# CableNodeRevG.net
KiCad netlist of a schematic drawn in Altium Designer
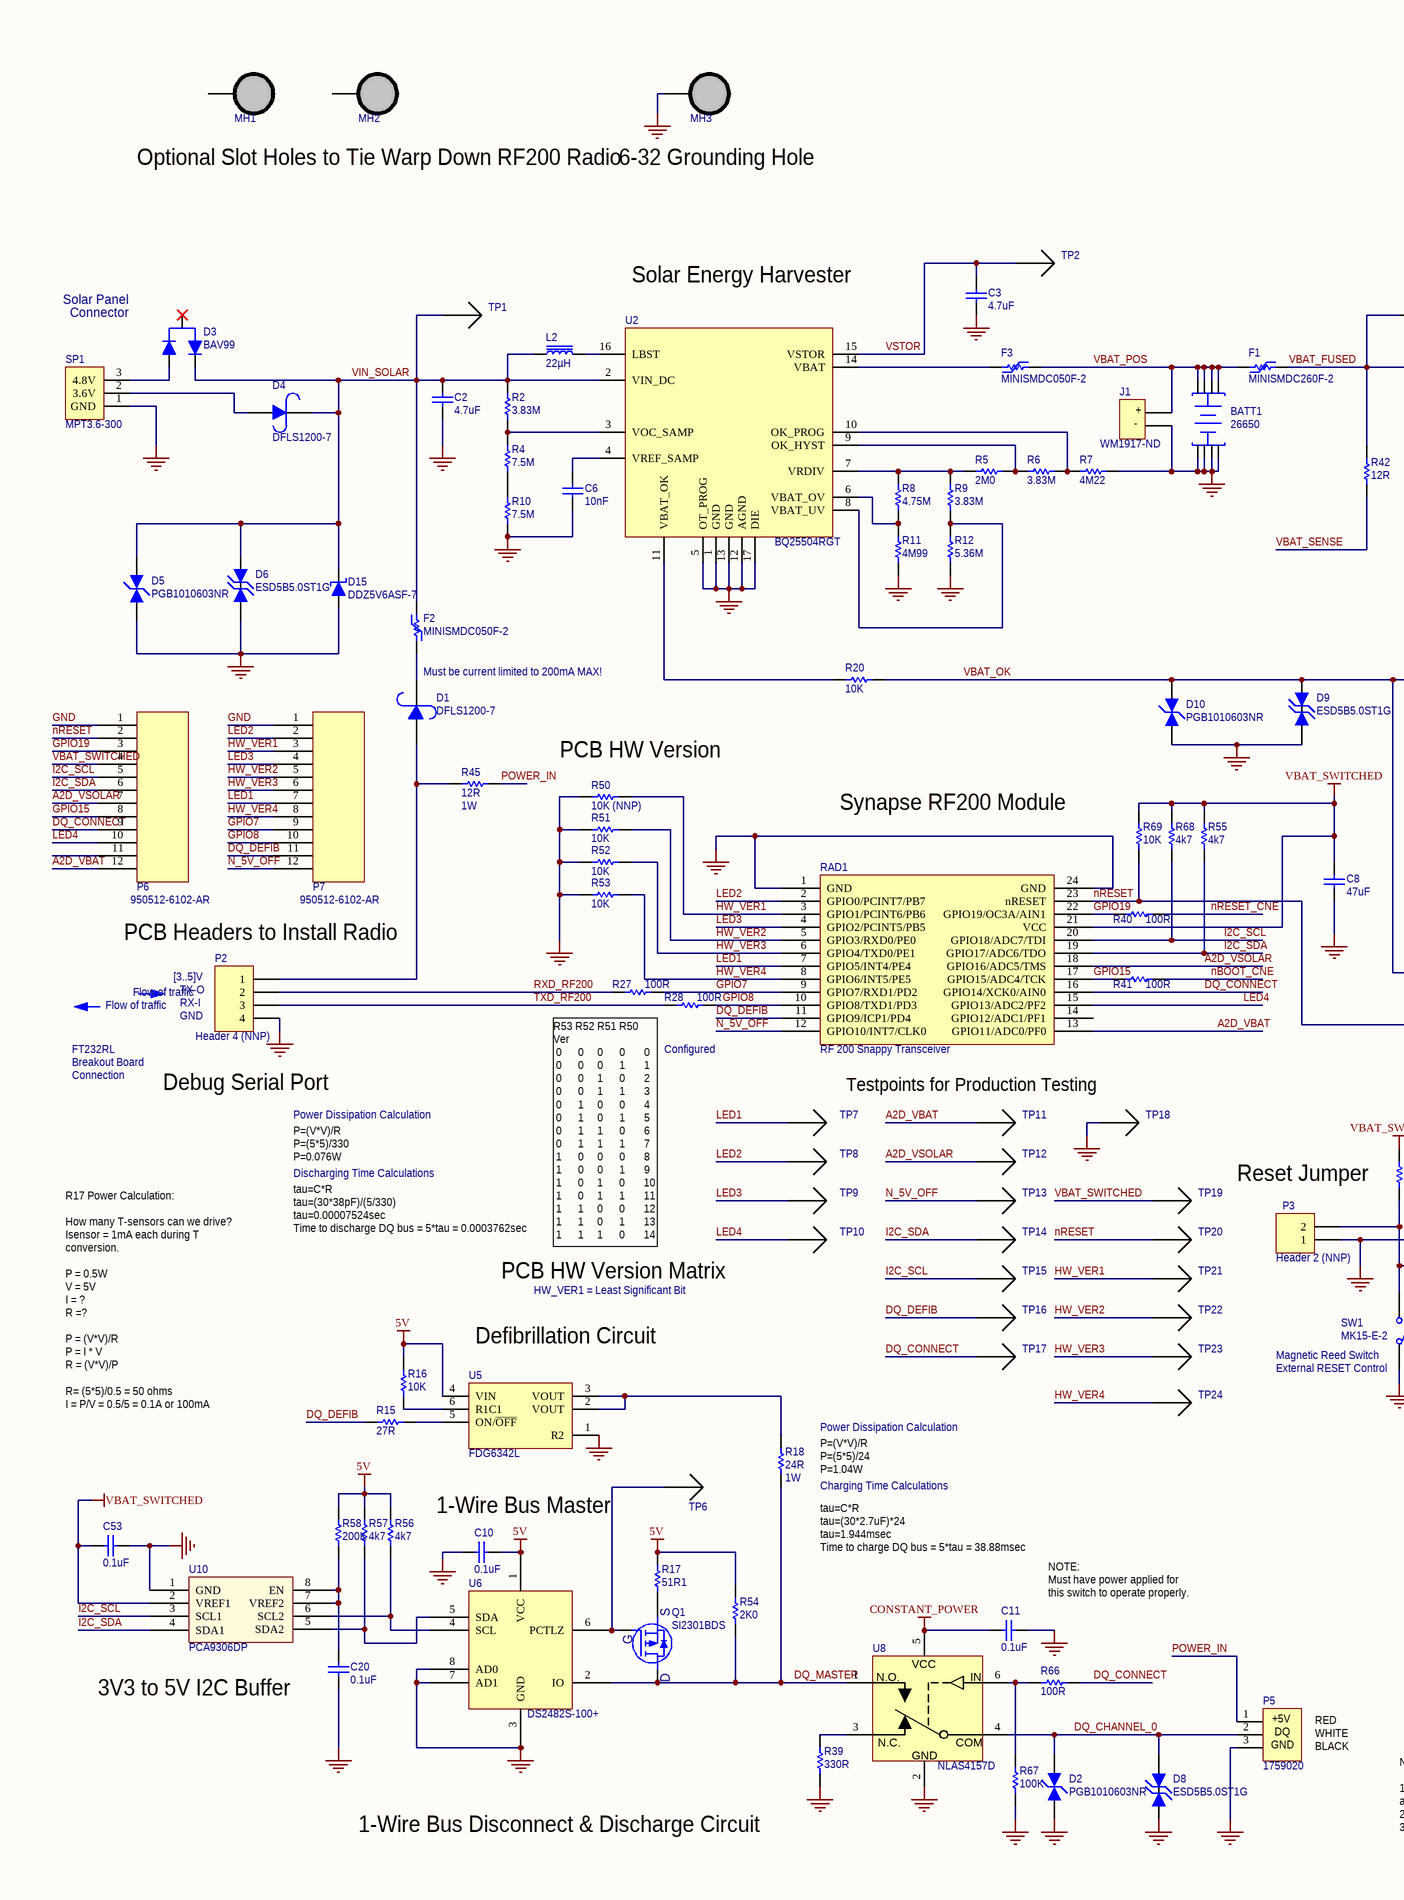
[diagram p0: CableNodeRevG.SchDoc, left]
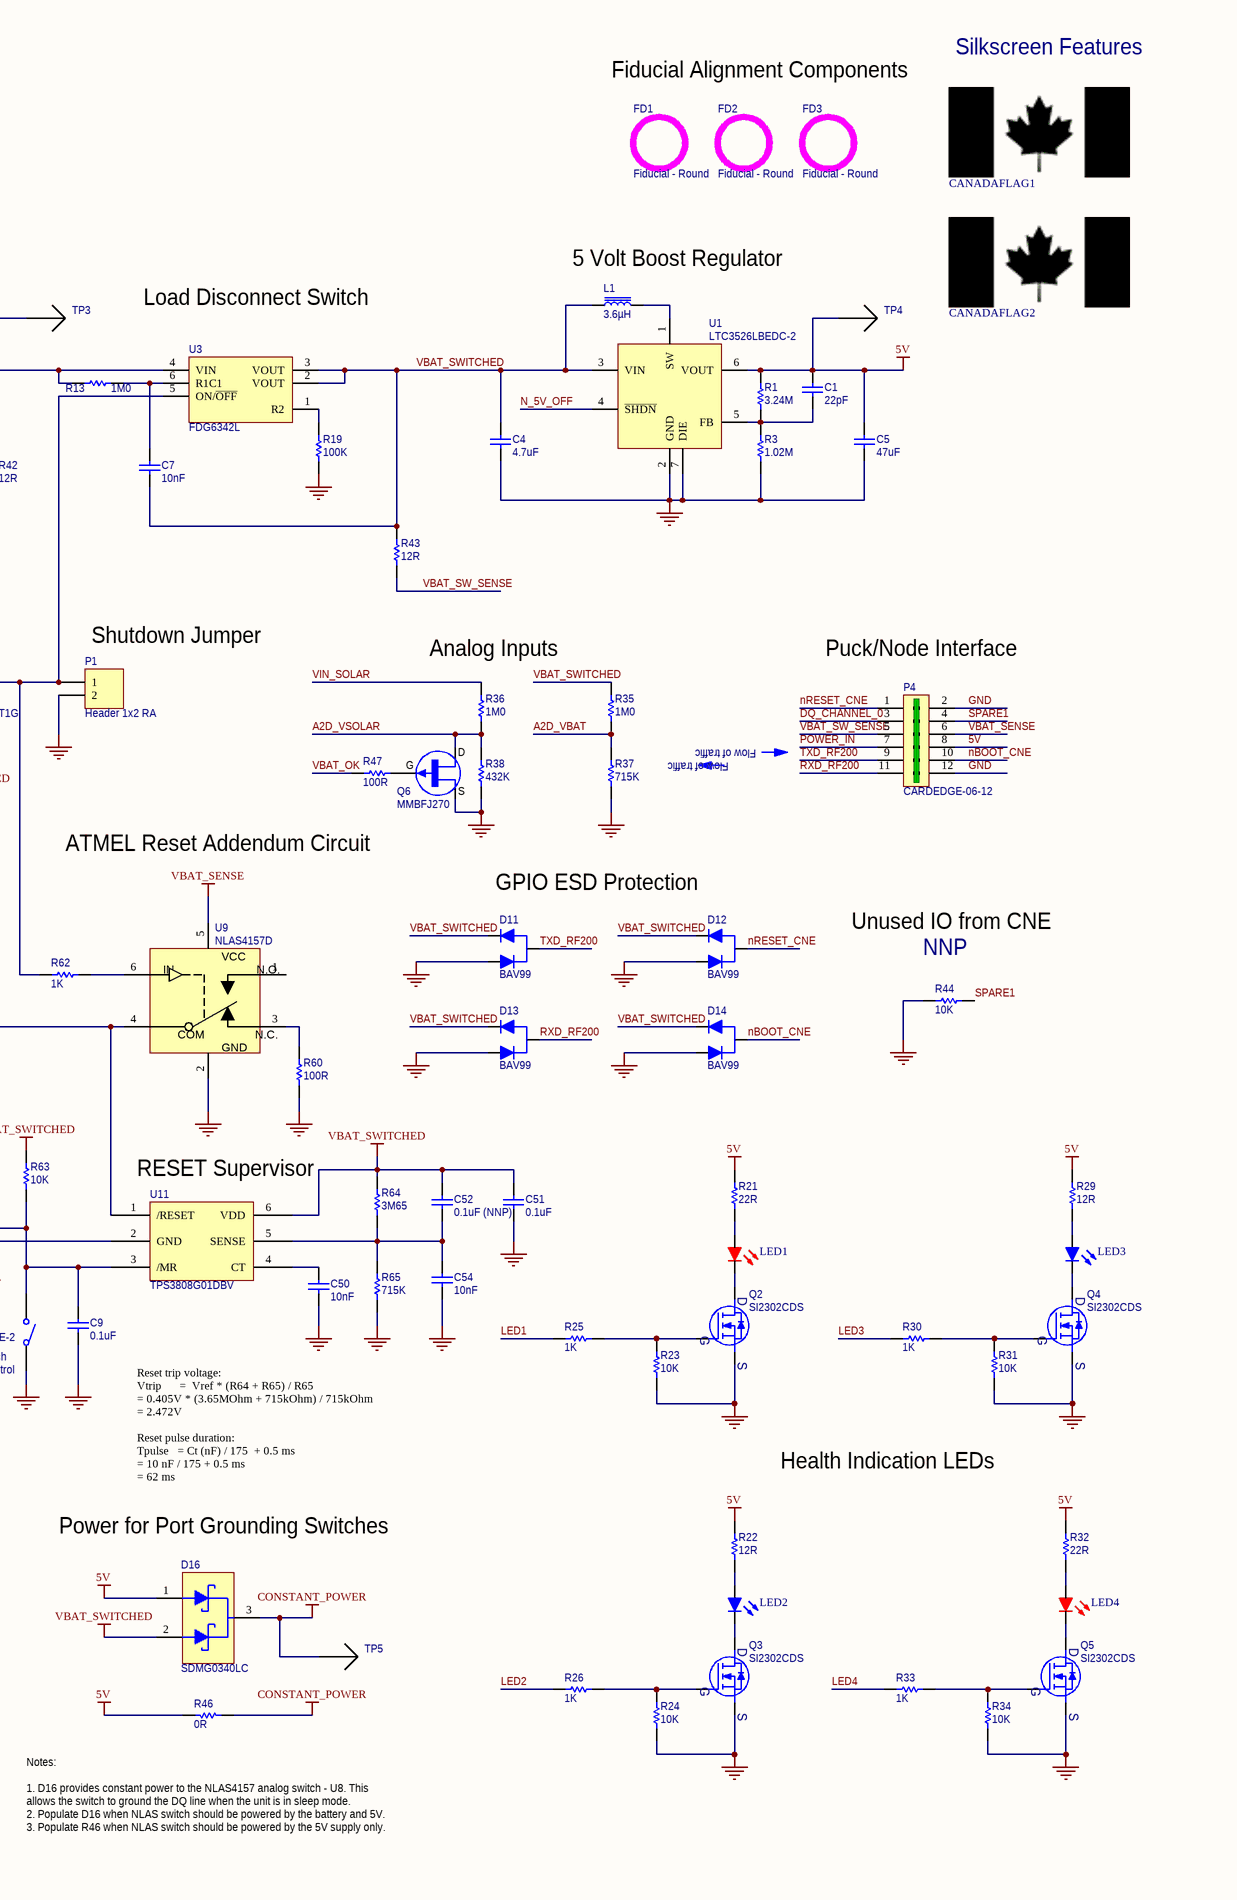
[diagram p1: CableNodeRevG.SchDoc, right]

(export (version "E")
  (design (tool "Eeschema 10.0.6"))
  (components
    (comp (ref "BATT1")
      (value "26650")
      (footprint "Battery_26650")
      (description "26650 LiFePO4 3.2V 3300mAh")
      (fields
        (field (name "MANUFACTURER") "TACBattery")
        (field (name "MANUFACTURER PART NUMBER") "26650 3.2V 1500mAh with wire")
      )
      (libsource (lib "Swage") (part "BATT_18650_1"))
    )
    (comp (ref "C1")
      (value "22pF")
      (footprint "RC0805")
      (description "CAP CER 22PF 50V 5% NPO 0805")
      (fields
        (field (name "MANUFACTURER") "Yageo")
        (field (name "MANUFACTURER PART NUMBER") "CC0805JRNPO9BN220")
      )
      (libsource (lib "Swage") (part "CC0805JRNPO9BN220"))
    )
    (comp (ref "C2")
      (value "4.7uF")
      (footprint "RC0805")
      (description "CAP CER 4.7UF 6.3V 10% X5R 0805")
      (fields
        (field (name "MANUFACTURER") "Taiyo Yuden")
        (field (name "MANUFACTURER PART NUMBER") "JMK212BJ475KG-T")
      )
      (libsource (lib "Swage") (part "JMK212BJ475KG-T"))
    )
    (comp (ref "C3")
      (value "4.7uF")
      (footprint "RC0805")
      (description "CAP CER 4.7UF 6.3V 10% X5R 0805")
      (fields
        (field (name "MANUFACTURER") "Taiyo Yuden")
        (field (name "MANUFACTURER PART NUMBER") "JMK212BJ475KG-T")
      )
      (libsource (lib "Swage") (part "JMK212BJ475KG-T"))
    )
    (comp (ref "C4")
      (value "4.7uF")
      (footprint "RC0805")
      (description "CAP CER 4.7UF 6.3V 10% X5R 0805")
      (fields
        (field (name "MANUFACTURER") "Taiyo Yuden")
        (field (name "MANUFACTURER PART NUMBER") "JMK212BJ475KG-T")
      )
      (libsource (lib "Swage") (part "JMK212BJ475KG-T"))
    )
    (comp (ref "C5")
      (value "47uF")
      (footprint "RC1206")
      (description "CAP CER 47UF 10V 20% X5R 1206")
      (fields
        (field (name "MANUFACTURER") "Taiyo Yuden")
        (field (name "MANUFACTURER PART NUMBER") "LMK316BJ476ML-T")
      )
      (libsource (lib "Swage") (part "LMK316BJ476ML-T"))
    )
    (comp (ref "C6")
      (value "10nF")
      (footprint "RC0805")
      (description "CAP CER 10000PF 100V X7R 0805")
      (fields
        (field (name "MANUFACTURER") "TDK Corporation")
        (field (name "MANUFACTURER PART NUMBER") "C2012X7R2A103K")
      )
      (libsource (lib "Swage") (part "C2012X7R2A103K"))
    )
    (comp (ref "C7")
      (value "10nF")
      (footprint "RC0603")
      (description "CAP CER 10000PF 50V 10% X7R 0603")
      (fields
        (field (name "MANUFACTURER") "TDK Corporation")
        (field (name "MANUFACTURER PART NUMBER") "C1608X7R1H103K")
      )
      (libsource (lib "Swage") (part "C1608X7R1H103K"))
    )
    (comp (ref "C8")
      (value "47uF")
      (footprint "RC1206")
      (description "CAP CER 47UF 10V 20% X5R 1206")
      (fields
        (field (name "MANUFACTURER") "Taiyo Yuden")
        (field (name "MANUFACTURER PART NUMBER") "LMK316BJ476ML-T")
      )
      (libsource (lib "Swage") (part "LMK316BJ476ML-T"))
    )
    (comp (ref "C9")
      (value "0.1uF")
      (footprint "RC0603")
      (description "CAP CERM .1UF 10% 16V X7R 0603")
      (fields
        (field (name "MANUFACTURER") "AVX Corporation")
        (field (name "MANUFACTURER PART NUMBER") "0603YC104KAT2A")
      )
      (libsource (lib "Swage") (part "0603YC104KAT2A"))
    )
    (comp (ref "C10")
      (value "0.1uF")
      (footprint "RC0603")
      (description "CAP CERM .1UF 10% 16V X7R 0603")
      (fields (field (name "TOLERANCE") "±10%") (field (name "MANUFACTURER PART NUMBER") "0603YC104KAT2A"))
      (libsource (lib "Swage") (part "0603YC104KAT2A"))
    )
    (comp (ref "C11")
      (value "0.1uF")
      (footprint "RC0603")
      (description "CAP CERM .1UF 10% 16V X7R 0603")
      (fields (field (name "TOLERANCE") "±10%") (field (name "MANUFACTURER PART NUMBER") "0603YC104KAT2A"))
      (libsource (lib "Swage") (part "0603YC104KAT2A"))
    )
    (comp (ref "C20")
      (value "0.1uF")
      (footprint "RC0603")
      (description "CAP CERM .1UF 10% 16V X7R 0603")
      (fields (field (name "TOLERANCE") "±10%") (field (name "MANUFACTURER PART NUMBER") "0603YC104KAT2A"))
      (libsource (lib "Swage") (part "0603YC104KAT2A"))
    )
    (comp (ref "C50")
      (value "10nF")
      (footprint "RC0603")
      (description "CAP CER 10000PF 50V 10% X7R 0603")
      (fields
        (field (name "MANUFACTURER") "TDK Corporation")
        (field (name "MANUFACTURER PART NUMBER") "C1608X7R1H103K")
      )
      (libsource (lib "Swage") (part "C1608X7R1H103K"))
    )
    (comp (ref "C51")
      (value "0.1uF")
      (footprint "RC0603")
      (description "CAP CERM .1UF 10% 16V X7R 0603")
      (fields (field (name "TOLERANCE") "±10%") (field (name "MANUFACTURER PART NUMBER") "0603YC104KAT2A"))
      (libsource (lib "Swage") (part "0603YC104KAT2A"))
    )
    (comp (ref "C52")
      (value "0.1uF (NNP)")
      (footprint "RC0603")
      (description "CAP CERM .1UF 10% 16V X7R 0603")
      (fields (field (name "TOLERANCE") "±10%") (field (name "MANUFACTURER PART NUMBER") "0603YC104KAT2A"))
      (libsource (lib "Swage") (part "0603YC104KAT2A"))
    )
    (comp (ref "C53")
      (value "0.1uF")
      (footprint "RC0603")
      (description "CAP CERM .1UF 10% 16V X7R 0603")
      (fields (field (name "TOLERANCE") "±10%") (field (name "MANUFACTURER PART NUMBER") "0603YC104KAT2A"))
      (libsource (lib "Swage") (part "0603YC104KAT2A"))
    )
    (comp (ref "C54")
      (value "10nF")
      (footprint "RC0603")
      (description "CAP CER 10000PF 50V 10% X7R 0603")
      (fields
        (field (name "MANUFACTURER") "TDK Corporation")
        (field (name "MANUFACTURER PART NUMBER") "C1608X7R1H103K")
      )
      (libsource (lib "Swage") (part "C1608X7R1H103K"))
    )
    (comp (ref "CANADAFLAG1")
      (value "Canada Flag")
      (footprint "CanadaFlag500x250")
      (libsource (lib "Swage") (part "CanadaFlag"))
    )
    (comp (ref "CANADAFLAG2")
      (value "Canada Flag")
      (footprint "CanadaFlag500x250")
      (libsource (lib "Swage") (part "CanadaFlag"))
    )
    (comp (ref "D1")
      (value "DFLS1200-7")
      (footprint "POWERDI-123")
      (description "DIODE SCHOTTKY 1A 200V PWRDI 123")
      (fields (field (name "MANUFACTURER") "Diodes Inc"))
      (libsource (lib "Swage") (part "DFLS1200-7"))
    )
    (comp (ref "D2")
      (value "PGB1010603NR")
      (footprint "RC0603")
      (description "SUPPRESSOR ESD 24VDC 0603 SMD")
      (fields (field (name "MANUFACTURER") "Littelfuse Inc"))
      (libsource (lib "Swage") (part "PGB1010603NR"))
    )
    (comp (ref "D3")
      (value "BAV99")
      (footprint "SOT23")
      (description "DIODE SW DUAL 75V 350MW SOT23-3")
      (fields
        (field (name "MANUFACTURER") "Diodes Inc")
        (field (name "MANUFACTURER PART NUMBER") "BAV99-7-F")
      )
      (libsource (lib "Swage") (part "BAV99-7-F"))
    )
    (comp (ref "D4")
      (value "DFLS1200-7")
      (footprint "POWERDI-123")
      (description "DIODE SCHOTTKY 1A 200V PWRDI 123")
      (fields (field (name "MANUFACTURER") "Diodes Inc"))
      (libsource (lib "Swage") (part "DFLS1200-7"))
    )
    (comp (ref "D5")
      (value "PGB1010603NR")
      (footprint "RC0603")
      (description "SUPPRESSOR ESD 24VDC 0603 SMD")
      (fields (field (name "MANUFACTURER") "Littelfuse Inc"))
      (libsource (lib "Swage") (part "PGB1010603NR"))
    )
    (comp (ref "D6")
      (value "ESD5B5.0ST1G")
      (footprint "SOD-523")
      (description "TVS BIDIRECT 50W SOD523")
      (fields (field (name "MANUFACTURER") "ON Semiconductor"))
      (libsource (lib "Swage") (part "ESD5B5.0ST1G"))
    )
    (comp (ref "D8")
      (value "ESD5B5.0ST1G")
      (footprint "SOD-523")
      (description "TVS BIDIRECT 50W SOD523")
      (fields (field (name "MANUFACTURER") "ON Semiconductor"))
      (libsource (lib "Swage") (part "ESD5B5.0ST1G"))
    )
    (comp (ref "D9")
      (value "ESD5B5.0ST1G")
      (footprint "SOD-523")
      (description "TVS BIDIRECT 50W SOD523")
      (fields (field (name "MANUFACTURER") "ON Semiconductor"))
      (libsource (lib "Swage") (part "ESD5B5.0ST1G"))
    )
    (comp (ref "D10")
      (value "PGB1010603NR")
      (footprint "RC0603")
      (description "SUPPRESSOR ESD 24VDC 0603 SMD")
      (fields (field (name "MANUFACTURER") "Littelfuse Inc"))
      (libsource (lib "Swage") (part "PGB1010603NR"))
    )
    (comp (ref "D11")
      (value "BAV99")
      (footprint "SOT23")
      (description "DIODE SW DUAL 75V 350MW SOT23-3")
      (fields
        (field (name "MANUFACTURER") "Diodes Inc")
        (field (name "MANUFACTURER PART NUMBER") "BAV99-7-F")
      )
      (libsource (lib "Swage") (part "BAV99-7-F"))
    )
    (comp (ref "D12")
      (value "BAV99")
      (footprint "SOT23")
      (description "DIODE SW DUAL 75V 350MW SOT23-3")
      (fields
        (field (name "MANUFACTURER") "Diodes Inc")
        (field (name "MANUFACTURER PART NUMBER") "BAV99-7-F")
      )
      (libsource (lib "Swage") (part "BAV99-7-F"))
    )
    (comp (ref "D13")
      (value "BAV99")
      (footprint "SOT23")
      (description "DIODE SW DUAL 75V 350MW SOT23-3")
      (fields
        (field (name "MANUFACTURER") "Diodes Inc")
        (field (name "MANUFACTURER PART NUMBER") "BAV99-7-F")
      )
      (libsource (lib "Swage") (part "BAV99-7-F"))
    )
    (comp (ref "D14")
      (value "BAV99")
      (footprint "SOT23")
      (description "DIODE SW DUAL 75V 350MW SOT23-3")
      (fields
        (field (name "MANUFACTURER") "Diodes Inc")
        (field (name "MANUFACTURER PART NUMBER") "BAV99-7-F")
      )
      (libsource (lib "Swage") (part "BAV99-7-F"))
    )
    (comp (ref "D15")
      (value "DDZ5V6ASF-7")
      (footprint "SOD323F")
      (description "DIODE ZENER 5.42V 500MW SOD323F")
      (fields (field (name "MANUFACTURER") "Diodes Inc") (field (name "TOLERANCE") "±2%"))
      (libsource (lib "Swage") (part "DDZ5V6ASF-7"))
    )
    (comp (ref "D16")
      (value "SDMG0340LC")
      (footprint "SOT-323")
      (description "DIODE SCHOTTKY 40V 30MA SOT323")
      (fields
        (field (name "MANUFACTURER") "Diodes Inc")
        (field (name "MANUFACTURER PART NUMBER") "SDMG0340LC-7-F")
      )
      (libsource (lib "Swage") (part "SDMG0340LC-7-F"))
    )
    (comp (ref "F1")
      (value "MINISMDC260F-2")
      (footprint "MINISMDC260F")
      (description "POLYSWITCH 2.6A RESET FUSE SMD")
      (fields (field (name "MANUFACTURER") "TE Connectivity"))
      (libsource (lib "Swage") (part "MINISMDC260F-2"))
    )
    (comp (ref "F2")
      (value "MINISMDC050F-2")
      (footprint "MINISMD050")
      (description "POLYSWITCH .50A RESET FUSE SMD")
      (fields (field (name "MANUFACTURER") "TE Connectivity"))
      (libsource (lib "Swage") (part "MINISMDC050F-2"))
    )
    (comp (ref "F3")
      (value "MINISMDC050F-2")
      (footprint "MINISMD050")
      (description "POLYSWITCH .50A RESET FUSE SMD")
      (fields (field (name "MANUFACTURER") "TE Connectivity"))
      (libsource (lib "Swage") (part "MINISMDC050F-2"))
    )
    (comp (ref "FD1")
      (value "Fiducial - Round")
      (footprint "FIDUCIAL ROUND SMALL")
      (description "Fiducial Round")
      (libsource (lib "StormaxV13") (part "Fiducial"))
    )
    (comp (ref "FD2")
      (value "Fiducial - Round")
      (footprint "FIDUCIAL ROUND SMALL")
      (description "Fiducial Round")
      (libsource (lib "StormaxV13") (part "Fiducial"))
    )
    (comp (ref "FD3")
      (value "Fiducial - Round")
      (footprint "FIDUCIAL ROUND SMALL")
      (description "Fiducial Round")
      (libsource (lib "StormaxV13") (part "Fiducial"))
    )
    (comp (ref "J1")
      (value "CONN")
      (footprint "BATTERYCONNECTOR")
      (description "CONN HEADER 2POS 3MM VERT GOLD")
      (fields
        (field (name "MANUFACTURER") "Molex Inc")
        (field (name "MANUFACTURER PART NUMBER") "436500216")
        (field (name "SUPPLIER PART NUMBER 1") "WM1917-ND")
      )
      (libsource (lib "Swage") (part "436500216"))
    )
    (comp (ref "L1")
      (value "3.6µH")
      (footprint "IND-WURTH")
      (description "INDUCTOR POWER 3.6UH 1.38A SMD")
      (fields
        (field (name "MANUFACTURER") "Wurth Electronics Inc")
        (field (name "MANUFACTURER PART NUMBER") "744031003")
      )
      (libsource (lib "Swage") (part "744031003"))
    )
    (comp (ref "L2")
      (value "22µH")
      (footprint "IND-SRR0604")
      (description "INDUCTOR PWR 22UH 20% SHIELD SMD")
      (fields
        (field (name "MANUFACTURER") "Bourns Inc.")
        (field (name "MANUFACTURER PART NUMBER") "SRR0604-220ML")
      )
      (libsource (lib "Swage") (part "SRR0604-220ML"))
    )
    (comp (ref "LED1")
      (value "GH_JTLPS1.24-K5L2-1-1-150-R33")
      (footprint "GHJTLPS124K5L211150R33")
      (description "LED")
      (fields
        (field (name "MANUFACTURER") "OSRAM")
        (field (name "MANUFACTURER PART NUMBER") "GH JTLPS1.24-K5L2-1-1-150-R33")
      )
      (libsource (lib "Swage") (part "GH_JTLPS1.24-K5L2-1-1-150-R33"))
    )
    (comp (ref "LED2")
      (value "GD JTLPS1.14-MFN8-25-1-150-R33")
      (footprint "GHJTLPS124K5L211150R33")
      (description "LED")
      (fields
        (field (name "MANUFACTURER") "OSRAM")
        (field (name "MANUFACTURER PART NUMBER") "GDJTLPS1.14-MFN8-25-1-150-R33")
      )
      (libsource (lib "Swage") (part "GH_JTLPS1.14-MFN8-25-1-150-R33"))
    )
    (comp (ref "LED3")
      (value "GD JTLPS1.14-MFN8-25-1-150-R33")
      (footprint "GHJTLPS124K5L211150R33")
      (description "LED")
      (fields
        (field (name "MANUFACTURER") "OSRAM")
        (field (name "MANUFACTURER PART NUMBER") "GDJTLPS1.14-MFN8-25-1-150-R33")
      )
      (libsource (lib "Swage") (part "GH_JTLPS1.14-MFN8-25-1-150-R33"))
    )
    (comp (ref "LED4")
      (value "GH_JTLPS1.24-K5L2-1-1-150-R33")
      (footprint "GHJTLPS124K5L211150R33")
      (description "LED")
      (fields
        (field (name "MANUFACTURER") "OSRAM")
        (field (name "MANUFACTURER PART NUMBER") "GH JTLPS1.24-K5L2-1-1-150-R33")
      )
      (libsource (lib "Swage") (part "GH_JTLPS1.24-K5L2-1-1-150-R33"))
    )
    (comp (ref "MH1")
      (value "MountingHole")
      (footprint "MountingHole")
      (description "PCB Mounting Hole, 0.150\" hole, 0.270\" Keepout")
      (libsource (lib "Swage") (part "MountingHole"))
    )
    (comp (ref "MH2")
      (value "MountingHole")
      (footprint "MountingHole")
      (description "PCB Mounting Hole, 0.150\" hole, 0.270\" Keepout")
      (libsource (lib "Swage") (part "MountingHole"))
    )
    (comp (ref "MH3")
      (value "MountingHole")
      (footprint "MountingHole")
      (description "PCB Mounting Hole, 0.150\" hole, 0.270\" Keepout")
      (libsource (lib "Swage") (part "MountingHole"))
    )
    (comp (ref "P1")
      (value "Header 1x2 RA")
      (footprint "HDR1X2")
      (description "SIL HORIZ PC TAIL PIN HEADER")
      (fields
        (field (name "MANUFACTURER") "Harwin Inc")
        (field (name "MANUFACTURER PART NUMBER") "M20-9960245")
      )
      (libsource (lib "Swage") (part "M20-9960245"))
    )
    (comp (ref "P2")
      (value "Header 4 (NNP)")
      (footprint "HDR1X4")
      (description "Header, 4-Pin")
      (fields
        (field (name "MANUFACTURER") "3M")
        (field (name "MANUFACTURER PART NUMBER") "2340-6111TG")
        (field (name "PUBLISHER") "Altium Limited")
      )
      (libsource (lib "Swage") (part "Header 4"))
    )
    (comp (ref "P3")
      (value "Header 2 (NNP)")
      (footprint "HDR1X2")
      (description "Header, 2-Pin")
      (fields
        (field (name "MANUFACTURER") "3M")
        (field (name "MANUFACTURER PART NUMBER") "2340-6111TG")
        (field (name "PUBLISHER") "Altium Limited")
      )
      (libsource (lib "Miscellaneous Connectors") (part "Header 2"))
    )
    (comp (ref "P4")
      (value "CARDEDGE-06-12")
      (footprint "EdgeConnectorFingers")
      (description "CONN EDGECARD 6POS .100 FINGERS")
      (libsource (lib "Swage") (part "CARDEDGE-06-12"))
    )
    (comp (ref "P5")
      (value "1759020")
      (footprint "PC-1759020")
      (description "CONN HEADER RT ANG 3POS 5.08MM")
      (fields (field (name "MANUFACTURER") "Phoenix Contact") (field (name "VOLTAGE") "300V"))
      (libsource (lib "Swage") (part "1759020"))
    )
    (comp (ref "P6")
      (value "3M-950512-6102-AR")
      (footprint "HEADER1X12-2MM")
      (description "CONN SOCKET 12POS 2MM VERT T/H")
      (fields (field (name "MANUFACTURER") "3M") (field (name "MANUFACTURER PART NUMBER") "950512-6102-AR"))
      (libsource (lib "Swage") (part "3M-950512-6102-AR"))
    )
    (comp (ref "P7")
      (value "3M-950512-6102-AR")
      (footprint "HEADER1X12-2MM")
      (description "CONN SOCKET 12POS 2MM VERT T/H")
      (fields (field (name "MANUFACTURER") "3M") (field (name "MANUFACTURER PART NUMBER") "950512-6102-AR"))
      (libsource (lib "Swage") (part "3M-950512-6102-AR"))
    )
    (comp (ref "Q1")
      (value "SI2301BDS")
      (footprint "SOT23(DGS)")
      (description "MOSFET P-CH 20V 2.2A SOT23-3")
      (fields
        (field (name "MANUFACTURER") "Vishay/Siliconix")
        (field (name "MANUFACTURER PART NUMBER") "SI2301BDS-T1-E3")
      )
      (libsource (lib "Swage") (part "SI2301BDS-T1-E3"))
    )
    (comp (ref "Q2")
      (value "SI2302CDS")
      (footprint "SOT23")
      (description "MOSFET N-CH 20V 2.6A SOT23-3")
      (fields
        (field (name "MANUFACTURER") "Vishay Siliconix")
        (field (name "MANUFACTURER PART NUMBER") "SI2302CDS-T1-GE3")
      )
      (libsource (lib "Swage") (part "SI2302CDS-T1-GE3"))
    )
    (comp (ref "Q3")
      (value "SI2302CDS")
      (footprint "SOT23")
      (description "MOSFET N-CH 20V 2.6A SOT23-3")
      (fields
        (field (name "MANUFACTURER") "Vishay Siliconix")
        (field (name "MANUFACTURER PART NUMBER") "SI2302CDS-T1-GE3")
      )
      (libsource (lib "Swage") (part "SI2302CDS-T1-GE3"))
    )
    (comp (ref "Q4")
      (value "SI2302CDS")
      (footprint "SOT23")
      (description "MOSFET N-CH 20V 2.6A SOT23-3")
      (fields
        (field (name "MANUFACTURER") "Vishay Siliconix")
        (field (name "MANUFACTURER PART NUMBER") "SI2302CDS-T1-GE3")
      )
      (libsource (lib "Swage") (part "SI2302CDS-T1-GE3"))
    )
    (comp (ref "Q5")
      (value "SI2302CDS")
      (footprint "SOT23")
      (description "MOSFET N-CH 20V 2.6A SOT23-3")
      (fields
        (field (name "MANUFACTURER") "Vishay Siliconix")
        (field (name "MANUFACTURER PART NUMBER") "SI2302CDS-T1-GE3")
      )
      (libsource (lib "Swage") (part "SI2302CDS-T1-GE3"))
    )
    (comp (ref "Q6")
      (value "MMBFJ270")
      (footprint "SOT23")
      (description "IC SWITCH P-CHANNEL SOT-23")
      (fields (field (name "MANUFACTURER") "Fairchild Semiconductor"))
      (libsource (lib "Swage") (part "MMBFJ270"))
    )
    (comp (ref "R1")
      (value "3.24M")
      (footprint "RC0805")
      (description "RES 3.24M OHM 1/8W 1% 0805 SMD")
      (fields
        (field (name "MANUFACTURER") "Vishay Dale")
        (field (name "MANUFACTURER PART NUMBER") "CRCW08053M24FKEA")
      )
      (libsource (lib "Swage") (part "CRCW08053M24FKEA"))
    )
    (comp (ref "R2")
      (value "3.83M")
      (footprint "RC0603")
      (description "RES 3.83M OHM 1/10W 1% 0603 SMD")
      (fields
        (field (name "MANUFACTURER") "Vishay Dale")
        (field (name "MANUFACTURER PART NUMBER") "CRCW06033M83FKEA")
      )
      (libsource (lib "Swage") (part "CRCW06033M83FKEA"))
    )
    (comp (ref "R3")
      (value "1.02M")
      (footprint "RC0805")
      (description "RES 1.02M OHM 1/8W 1% 0805 SMD")
      (fields
        (field (name "MANUFACTURER") "Vishay Dale")
        (field (name "MANUFACTURER PART NUMBER") "CRCW08051M02FKEA")
      )
      (libsource (lib "Swage") (part "CRCW08051M02FKEA"))
    )
    (comp (ref "R4")
      (value "7.5M")
      (footprint "RC0603")
      (description "RES 7.50M OHM 1/10W 1% 0603 SMD")
      (fields
        (field (name "MANUFACTURER") "Vishay Dale")
        (field (name "MANUFACTURER PART NUMBER") "CRCW06037M50FKEA")
      )
      (libsource (lib "Swage") (part "CRCW06037M50FKEA"))
    )
    (comp (ref "R5")
      (value "2M0")
      (footprint "RC0603")
      (description "RES 2.00M OHM 1/10W 1% 0603 SMD")
      (fields
        (field (name "MANUFACTURER") "Vishay Dale")
        (field (name "MANUFACTURER PART NUMBER") "CRCW06032M00FKEA")
      )
      (libsource (lib "Swage") (part "CRCW06032M00FKEA"))
    )
    (comp (ref "R6")
      (value "3.83M")
      (footprint "RC0603")
      (description "RES 3.83M OHM 1/10W 1% 0603 SMD")
      (fields
        (field (name "MANUFACTURER") "Vishay Dale")
        (field (name "MANUFACTURER PART NUMBER") "CRCW06033M83FKEA")
      )
      (libsource (lib "Swage") (part "CRCW06033M83FKEA"))
    )
    (comp (ref "R7")
      (value "4M22")
      (footprint "RC0603")
      (description "RES 4.22M OHM 1/10W 1% 0603 SMD")
      (fields
        (field (name "MANUFACTURER") "Vishay Dale")
        (field (name "MANUFACTURER PART NUMBER") "CRCW06034M22FKEA")
      )
      (libsource (lib "Swage") (part "CRCW06034M22FKEA"))
    )
    (comp (ref "R8")
      (value "4.75M")
      (footprint "rc0603")
      (description "RES 4.75M OHM 1/10W 1% 0603 SMD")
      (fields
        (field (name "MANUFACTURER") "Vishay Dale")
        (field (name "MANUFACTURER PART NUMBER") "CRCW06034M75FKEA")
      )
      (libsource (lib "Swage") (part "CRCW06034M75FKEA"))
    )
    (comp (ref "R9")
      (value "3.83M")
      (footprint "RC0603")
      (description "RES 3.83M OHM 1/10W 1% 0603 SMD")
      (fields
        (field (name "MANUFACTURER") "Vishay Dale")
        (field (name "MANUFACTURER PART NUMBER") "CRCW06033M83FKEA")
      )
      (libsource (lib "Swage") (part "CRCW06033M83FKEA"))
    )
    (comp (ref "R10")
      (value "7.5M")
      (footprint "RC0603")
      (description "RES 7.50M OHM 1/10W 1% 0603 SMD")
      (fields
        (field (name "MANUFACTURER") "Vishay Dale")
        (field (name "MANUFACTURER PART NUMBER") "CRCW06037M50FKEA")
      )
      (libsource (lib "Swage") (part "CRCW06037M50FKEA"))
    )
    (comp (ref "R11")
      (value "4M99")
      (footprint "rc0603")
      (description "RES 4.99M OHM 1/10W 1% 0603 SMD")
      (fields
        (field (name "MANUFACTURER") "Vishay Dale")
        (field (name "MANUFACTURER PART NUMBER") "CRCW06034M99FKEA")
      )
      (libsource (lib "Swage") (part "CRCW06034M99FKEA"))
    )
    (comp (ref "R12")
      (value "5.36M")
      (footprint "RC0603")
      (description "RES 5.36M OHM 1/10W 1% 0603 SMD")
      (fields
        (field (name "MANUFACTURER") "Vishay Dale")
        (field (name "MANUFACTURER PART NUMBER") "CRCW06035M36FKEA")
      )
      (libsource (lib "Swage") (part "CRCW06035M36FKEA (2)"))
    )
    (comp (ref "R13")
      (value "1M0")
      (footprint "RESC1608X06N")
      (description "RES 1.0M OHM 1/10W 5% 0603 SMD")
      (fields (field (name "TOLERANCE") "±5%") (field (name "MANUFACTURER") "Panasonic - ECG"))
      (libsource (lib "Swage") (part "ERJ-3GEYJ105V"))
    )
    (comp (ref "R15")
      (value "27R")
      (footprint "RC0603")
      (description "RES 27.0 OHM 1/10W 1% 0603 SMD")
      (fields
        (field (name "MANUFACTURER") "Panasonic Electronic Components")
        (field (name "MANUFACTURER PART NUMBER") "ERJ-3EKF27R0V")
      )
      (libsource (lib "Swage") (part "ERJ-3EKF27R0V"))
    )
    (comp (ref "R16")
      (value "10K")
      (footprint "RC0603")
      (description "RES 10K OHM 1/10W 5% 0603 SMD")
      (fields
        (field (name "MANUFACTURER") "Panasonic Electronic Components")
        (field (name "MANUFACTURER PART NUMBER") "ERJ-3GEYJ103V")
      )
      (libsource (lib "Swage") (part "ERJ-3GEYJ103V"))
    )
    (comp (ref "R17")
      (value "51R1")
      (footprint "RC3225X07N")
      (description "RES 51.1 OHM 1/2W 1% 1210 SMD")
      (fields
        (field (name "MANUFACTURER") "Panasonic Electronic Components")
        (field (name "MANUFACTURER PART NUMBER") "ERJ-14NF51R1U")
      )
      (libsource (lib "Swage") (part "ERJ-14NF51R1U"))
    )
    (comp (ref "R18")
      (value "24R")
      (footprint "RES2512")
      (description "RES 24 OHM 1W 5% 2512 SMD")
      (fields
        (field (name "MANUFACTURER") "TTI Inc.")
        (field (name "MANUFACTURER PART NUMBER") "CRCW251224R0JNEG")
        (field (name "POWER (WATTS)") "1W")
      )
      (libsource (lib "Swage") (part "RMCF2512JT24R0"))
    )
    (comp (ref "R19")
      (value "100K")
      (footprint "RC0603")
      (description "RES 100K OHM 1/10W 5% 0603 SMD")
      (fields
        (field (name "MANUFACTURER") "Panasonic Electronic Components")
        (field (name "MANUFACTURER PART NUMBER") "ERJ-3GEYJ104V")
      )
      (libsource (lib "Swage") (part "ERJ-3GEYJ104V"))
    )
    (comp (ref "R20")
      (value "10K")
      (footprint "RC0603")
      (description "RES 10K OHM 1/10W 5% 0603 SMD")
      (fields
        (field (name "MANUFACTURER") "Panasonic Electronic Components")
        (field (name "MANUFACTURER PART NUMBER") "ERJ-3GEYJ103V")
      )
      (libsource (lib "Swage") (part "ERJ-3GEYJ103V"))
    )
    (comp (ref "R21")
      (value "22R")
      (footprint "RC1206")
      (description "RES 22.0 OHM 1/4W 1% 1206 SMD")
      (fields
        (field (name "MANUFACTURER") "Yageo")
        (field (name "MANUFACTURER PART NUMBER") "RC1206FR-0722RL")
      )
      (libsource (lib "Swage") (part "RC1206FR-0722RL"))
    )
    (comp (ref "R22")
      (value "12R")
      (footprint "RC1206")
      (description "RES 12.0 OHM 1/4W 1% 1206 SMD")
      (fields
        (field (name "MANUFACTURER") "Yageo")
        (field (name "MANUFACTURER PART NUMBER") "RC1206FR-0712RL")
      )
      (libsource (lib "Swage") (part "RC1206FR-0712RL"))
    )
    (comp (ref "R23")
      (value "10K")
      (footprint "RC0603")
      (description "RES 10K OHM 1/10W 5% 0603 SMD")
      (fields
        (field (name "MANUFACTURER") "Panasonic Electronic Components")
        (field (name "MANUFACTURER PART NUMBER") "ERJ-3GEYJ103V")
      )
      (libsource (lib "Swage") (part "ERJ-3GEYJ103V"))
    )
    (comp (ref "R24")
      (value "10K")
      (footprint "RC0603")
      (description "RES 10K OHM 1/10W 5% 0603 SMD")
      (fields
        (field (name "MANUFACTURER") "Panasonic Electronic Components")
        (field (name "MANUFACTURER PART NUMBER") "ERJ-3GEYJ103V")
      )
      (libsource (lib "Swage") (part "ERJ-3GEYJ103V"))
    )
    (comp (ref "R25")
      (value "1K")
      (footprint "rc0603")
      (description "RES 1.0K OHM 1/10W 5% 0603 SMD")
      (fields
        (field (name "MANUFACTURER") "Panasonic Electronic Components")
        (field (name "MANUFACTURER PART NUMBER") "ERJ-3GEYJ102V")
      )
      (libsource (lib "Swage") (part "ERJ-3GEYJ102V"))
    )
    (comp (ref "R26")
      (value "1K")
      (footprint "rc0603")
      (description "RES 1.0K OHM 1/10W 5% 0603 SMD")
      (fields
        (field (name "MANUFACTURER") "Panasonic Electronic Components")
        (field (name "MANUFACTURER PART NUMBER") "ERJ-3GEYJ102V")
      )
      (libsource (lib "Swage") (part "ERJ-3GEYJ102V"))
    )
    (comp (ref "R27")
      (value "100R")
      (footprint "RC0603")
      (description "RES 100 OHM 1/10W 5% 0603 SMD")
      (fields
        (field (name "TOLERANCE") "±5%")
        (field (name "MANUFACTURER") "Panasonic Electronic Components")
      )
      (libsource (lib "Swage") (part "ERJ-3GEYJ101V"))
    )
    (comp (ref "R28")
      (value "100R")
      (footprint "RC0603")
      (description "RES 100 OHM 1/10W 5% 0603 SMD")
      (fields
        (field (name "TOLERANCE") "±5%")
        (field (name "MANUFACTURER") "Panasonic Electronic Components")
      )
      (libsource (lib "Swage") (part "ERJ-3GEYJ101V"))
    )
    (comp (ref "R29")
      (value "12R")
      (footprint "RC1206")
      (description "RES 12.0 OHM 1/4W 1% 1206 SMD")
      (fields
        (field (name "MANUFACTURER") "Yageo")
        (field (name "MANUFACTURER PART NUMBER") "RC1206FR-0712RL")
      )
      (libsource (lib "Swage") (part "RC1206FR-0712RL"))
    )
    (comp (ref "R30")
      (value "1K")
      (footprint "rc0603")
      (description "RES 1.0K OHM 1/10W 5% 0603 SMD")
      (fields
        (field (name "MANUFACTURER") "Panasonic Electronic Components")
        (field (name "MANUFACTURER PART NUMBER") "ERJ-3GEYJ102V")
      )
      (libsource (lib "Swage") (part "ERJ-3GEYJ102V"))
    )
    (comp (ref "R31")
      (value "10K")
      (footprint "RC0603")
      (description "RES 10K OHM 1/10W 5% 0603 SMD")
      (fields
        (field (name "MANUFACTURER") "Panasonic Electronic Components")
        (field (name "MANUFACTURER PART NUMBER") "ERJ-3GEYJ103V")
      )
      (libsource (lib "Swage") (part "ERJ-3GEYJ103V"))
    )
    (comp (ref "R32")
      (value "22R")
      (footprint "RC1206")
      (description "RES 22.0 OHM 1/4W 1% 1206 SMD")
      (fields
        (field (name "MANUFACTURER") "Yageo")
        (field (name "MANUFACTURER PART NUMBER") "RC1206FR-0722RL")
      )
      (libsource (lib "Swage") (part "RC1206FR-0722RL"))
    )
    (comp (ref "R33")
      (value "1K")
      (footprint "rc0603")
      (description "RES 1.0K OHM 1/10W 5% 0603 SMD")
      (fields
        (field (name "MANUFACTURER") "Panasonic Electronic Components")
        (field (name "MANUFACTURER PART NUMBER") "ERJ-3GEYJ102V")
      )
      (libsource (lib "Swage") (part "ERJ-3GEYJ102V"))
    )
    (comp (ref "R34")
      (value "10K")
      (footprint "RC0603")
      (description "RES 10K OHM 1/10W 5% 0603 SMD")
      (fields
        (field (name "MANUFACTURER") "Panasonic Electronic Components")
        (field (name "MANUFACTURER PART NUMBER") "ERJ-3GEYJ103V")
      )
      (libsource (lib "Swage") (part "ERJ-3GEYJ103V"))
    )
    (comp (ref "R35")
      (value "1M0")
      (footprint "rc0603")
      (description "RES 1.00M OHM 1/10W 1% 0603 SMD")
      (fields
        (field (name "MANUFACTURER") "Panasonic Electronic Components")
        (field (name "MANUFACTURER PART NUMBER") "ERJ-3EKF1004V")
      )
      (libsource (lib "Swage") (part "ERJ-3EKF1004V"))
    )
    (comp (ref "R36")
      (value "1M0")
      (footprint "rc0603")
      (description "RES 1.00M OHM 1/10W 1% 0603 SMD")
      (fields
        (field (name "MANUFACTURER") "Panasonic Electronic Components")
        (field (name "MANUFACTURER PART NUMBER") "ERJ-3EKF1004V")
      )
      (libsource (lib "Swage") (part "ERJ-3EKF1004V"))
    )
    (comp (ref "R37")
      (value "715K")
      (footprint "RC0603")
      (description "RES 715K OHM 1/10W 1% 0603 SMD")
      (fields
        (field (name "MANUFACTURER") "Panasonic Electronic Components")
        (field (name "MANUFACTURER PART NUMBER") "ERJ-3EKF7153V")
      )
      (libsource (lib "Swage") (part "ERJ-3EKF7153V"))
    )
    (comp (ref "R38")
      (value "432K")
      (footprint "RC0603")
      (description "RES 432K OHM 1/10W 1% 0603 SMD")
      (fields
        (field (name "MANUFACTURER") "Panasonic Electronic Components")
        (field (name "MANUFACTURER PART NUMBER") "ERJ-3EKF4323V")
      )
      (libsource (lib "Swage") (part "ERJ-3EKF4323V"))
    )
    (comp (ref "R39")
      (value "330R")
      (footprint "RC0805")
      (description "RES 330 OHM 1/8W 5% 0805 SMD")
      (fields
        (field (name "MANUFACTURER") "KOA Speer Electronics")
        (field (name "MANUFACTURER PART NUMBER") "RK73B2ATTD331J")
      )
      (libsource (lib "Swage") (part "ERJ-6GEYJ331V"))
    )
    (comp (ref "R40")
      (value "100R")
      (footprint "RC0603")
      (description "RES 100 OHM 1/10W 5% 0603 SMD")
      (fields
        (field (name "TOLERANCE") "±5%")
        (field (name "MANUFACTURER") "Panasonic Electronic Components")
      )
      (libsource (lib "Swage") (part "ERJ-3GEYJ101V"))
    )
    (comp (ref "R41")
      (value "100R")
      (footprint "RC0603")
      (description "RES 100 OHM 1/10W 5% 0603 SMD")
      (fields
        (field (name "TOLERANCE") "±5%")
        (field (name "MANUFACTURER") "Panasonic Electronic Components")
      )
      (libsource (lib "Swage") (part "ERJ-3GEYJ101V"))
    )
    (comp (ref "R42")
      (value "12R")
      (footprint "RC1206")
      (description "RES 12.0 OHM 1/4W 1% 1206 SMD")
      (fields
        (field (name "MANUFACTURER") "Yageo")
        (field (name "MANUFACTURER PART NUMBER") "RC1206FR-0712RL")
      )
      (libsource (lib "Swage") (part "RC1206FR-0712RL"))
    )
    (comp (ref "R43")
      (value "12R")
      (footprint "RC1206")
      (description "RES 12.0 OHM 1/4W 1% 1206 SMD")
      (fields
        (field (name "MANUFACTURER") "Yageo")
        (field (name "MANUFACTURER PART NUMBER") "RC1206FR-0712RL")
      )
      (libsource (lib "Swage") (part "RC1206FR-0712RL"))
    )
    (comp (ref "R44")
      (value "10K")
      (footprint "RC0603")
      (description "RES 10K OHM 1/10W 5% 0603 SMD")
      (fields
        (field (name "MANUFACTURER") "Panasonic Electronic Components")
        (field (name "MANUFACTURER PART NUMBER") "ERJ-3GEYJ103V")
      )
      (libsource (lib "Swage") (part "ERJ-3GEYJ103V"))
    )
    (comp (ref "R45")
      (value "12R")
      (footprint "RES2512")
      (description "RES 12 OHM 1W 5% 2512")
      (fields
        (field (name "MANUFACTURER") "Stackpole Electronics Inc")
        (field (name "MANUFACTURER PART NUMBER") "RPC2512JT12R0")
        (field (name "POWER (WATTS)") "1W")
      )
      (libsource (lib "Swage") (part "RPC2512JT12R0"))
    )
    (comp (ref "R46")
      (value "0R")
      (footprint "RC0603")
      (description "RES 0.0 OHM 1/10W 0603 SMD")
      (fields (field (name "TOLERANCE") "Jumper") (field (name "MANUFACTURER") "Panasonic - ECG"))
      (libsource (lib "Swage") (part "ERJ-3GEY0R00V"))
    )
    (comp (ref "R47")
      (value "100R")
      (footprint "RC0603")
      (description "RES 100 OHM 1/10W 5% 0603 SMD")
      (fields
        (field (name "TOLERANCE") "±5%")
        (field (name "MANUFACTURER") "Panasonic Electronic Components")
      )
      (libsource (lib "Swage") (part "ERJ-3GEYJ101V"))
    )
    (comp (ref "R50")
      (value "10K (NNP)")
      (footprint "RC0603")
      (description "RES 10K OHM 1/10W 5% 0603 SMD")
      (fields
        (field (name "MANUFACTURER") "Panasonic Electronic Components")
        (field (name "MANUFACTURER PART NUMBER") "ERJ-3GEYJ103V")
      )
      (libsource (lib "Swage") (part "ERJ-3GEYJ103V"))
    )
    (comp (ref "R51")
      (value "10K")
      (footprint "RC0603")
      (description "RES 10K OHM 1/10W 5% 0603 SMD")
      (fields
        (field (name "MANUFACTURER") "Panasonic Electronic Components")
        (field (name "MANUFACTURER PART NUMBER") "ERJ-3GEYJ103V")
      )
      (libsource (lib "Swage") (part "ERJ-3GEYJ103V"))
    )
    (comp (ref "R52")
      (value "10K")
      (footprint "RC0603")
      (description "RES 10K OHM 1/10W 5% 0603 SMD")
      (fields
        (field (name "MANUFACTURER") "Panasonic Electronic Components")
        (field (name "MANUFACTURER PART NUMBER") "ERJ-3GEYJ103V")
      )
      (libsource (lib "Swage") (part "ERJ-3GEYJ103V"))
    )
    (comp (ref "R53")
      (value "10K")
      (footprint "RC0603")
      (description "RES 10K OHM 1/10W 5% 0603 SMD")
      (fields
        (field (name "MANUFACTURER") "Panasonic Electronic Components")
        (field (name "MANUFACTURER PART NUMBER") "ERJ-3GEYJ103V")
      )
      (libsource (lib "Swage") (part "ERJ-3GEYJ103V"))
    )
    (comp (ref "R54")
      (value "2K0")
      (footprint "RC0603")
      (description "RES 2K OHM 1/10W 1% 0603 SMD")
      (fields
        (field (name "MANUFACTURER") "Panasonic Electronic Components")
        (field (name "MANUFACTURER PART NUMBER") "ERJ-3EKF2001V")
      )
      (libsource (lib "Swage") (part "ERJ-3EKF2001V"))
    )
    (comp (ref "R55")
      (value "4k7")
      (footprint "RC0603")
      (description "RES 4.7K OHM 1/10W 5% 0603 SMD")
      (fields
        (field (name "MANUFACTURER") "Panasonic - ECG")
        (field (name "MANUFACTURER PART NUMBER") "ERJ-3GEYJ472V")
      )
      (libsource (lib "Swage") (part "ERJ-3GEYJ472V"))
    )
    (comp (ref "R56")
      (value "4k7")
      (footprint "RC0603")
      (description "RES 4.7K OHM 1/10W 5% 0603 SMD")
      (fields
        (field (name "MANUFACTURER") "Panasonic - ECG")
        (field (name "MANUFACTURER PART NUMBER") "ERJ-3GEYJ472V")
      )
      (libsource (lib "Swage") (part "ERJ-3GEYJ472V"))
    )
    (comp (ref "R57")
      (value "4k7")
      (footprint "RC0603")
      (description "RES 4.7K OHM 1/10W 5% 0603 SMD")
      (fields
        (field (name "MANUFACTURER") "Panasonic - ECG")
        (field (name "MANUFACTURER PART NUMBER") "ERJ-3GEYJ472V")
      )
      (libsource (lib "Swage") (part "ERJ-3GEYJ472V"))
    )
    (comp (ref "R58")
      (value "200K")
      (footprint "RC0603")
      (description "RES 200K OHM 1/10W 5% 0603 SMD")
      (fields
        (field (name "MANUFACTURER") "Panasonic Electronic Components")
        (field (name "MANUFACTURER PART NUMBER") "ERJ-3GEYJ204V")
      )
      (libsource (lib "Swage") (part "ERJ-3GEYJ204V"))
    )
    (comp (ref "R60")
      (value "100R")
      (footprint "RC0603")
      (description "RES 100 OHM 1/10W 5% 0603 SMD")
      (fields
        (field (name "TOLERANCE") "±5%")
        (field (name "MANUFACTURER") "Panasonic Electronic Components")
      )
      (libsource (lib "Swage") (part "ERJ-3GEYJ101V"))
    )
    (comp (ref "R62")
      (value "1K")
      (footprint "rc0603")
      (description "RES 1.0K OHM 1/10W 5% 0603 SMD")
      (fields
        (field (name "MANUFACTURER") "Panasonic Electronic Components")
        (field (name "MANUFACTURER PART NUMBER") "ERJ-3GEYJ102V")
      )
      (libsource (lib "Swage") (part "ERJ-3GEYJ102V"))
    )
    (comp (ref "R63")
      (value "10K")
      (footprint "RC0603")
      (description "RES 10K OHM 1/10W 5% 0603 SMD")
      (fields
        (field (name "MANUFACTURER") "Panasonic Electronic Components")
        (field (name "MANUFACTURER PART NUMBER") "ERJ-3GEYJ103V")
      )
      (libsource (lib "Swage") (part "ERJ-3GEYJ103V"))
    )
    (comp (ref "R64")
      (value "3M65")
      (footprint "RC0603")
      (description "RES 3M65 OHM 1/10W 1% 0603 SMD")
      (fields
        (field (name "MANUFACTURER") "Samsung")
        (field (name "MANUFACTURER PART NUMBER") "RC1608F3654CS")
      )
      (libsource (lib "Swage") (part "RC1608F3654CS"))
    )
    (comp (ref "R65")
      (value "715K")
      (footprint "RC0603")
      (description "RES 715K OHM 1/10W 1% 0603 SMD")
      (fields
        (field (name "MANUFACTURER") "Panasonic Electronic Components")
        (field (name "MANUFACTURER PART NUMBER") "ERJ-3EKF7153V")
      )
      (libsource (lib "Swage") (part "ERJ-3EKF7153V"))
    )
    (comp (ref "R66")
      (value "100R")
      (footprint "RC0603")
      (description "RES 100 OHM 1/10W 5% 0603 SMD")
      (fields
        (field (name "TOLERANCE") "±5%")
        (field (name "MANUFACTURER") "Panasonic Electronic Components")
      )
      (libsource (lib "Swage") (part "ERJ-3GEYJ101V"))
    )
    (comp (ref "R67")
      (value "100K")
      (footprint "RC0603")
      (description "RES 100K OHM 1/10W 5% 0603 SMD")
      (fields
        (field (name "MANUFACTURER") "Panasonic Electronic Components")
        (field (name "MANUFACTURER PART NUMBER") "ERJ-3GEYJ104V")
      )
      (libsource (lib "Swage") (part "ERJ-3GEYJ104V"))
    )
    (comp (ref "R68")
      (value "4k7")
      (footprint "RC0603")
      (description "RES 4.7K OHM 1/10W 5% 0603 SMD")
      (fields
        (field (name "MANUFACTURER") "Panasonic - ECG")
        (field (name "MANUFACTURER PART NUMBER") "ERJ-3GEYJ472V")
      )
      (libsource (lib "Swage") (part "ERJ-3GEYJ472V"))
    )
    (comp (ref "R69")
      (value "10K")
      (footprint "RC0603")
      (description "RES 10K OHM 1/10W 5% 0603 SMD")
      (fields
        (field (name "MANUFACTURER") "Panasonic Electronic Components")
        (field (name "MANUFACTURER PART NUMBER") "ERJ-3GEYJ103V")
      )
      (libsource (lib "Swage") (part "ERJ-3GEYJ103V"))
    )
    (comp (ref "RAD1")
      (value "RF 200 Snappy Transceiver")
      (footprint "RF200")
      (description "Synapse RF200PF1 Snappy Transceiver")
      (fields
        (field (name "MANUFACTURER") "Synapse Wireless")
        (field (name "MANUFACTURER PART NUMBER") "RF200PF1")
      )
      (libsource (lib "Swage") (part "RF 200 Snappy Transceiver"))
    )
    (comp (ref "SP1")
      (value "MPT3.6-300")
      (footprint "SOLAR_PANEL_FLEX")
      (description "Solar Panel, Flexible, 3.6V and 4.8V footprints")
      (fields (field (name "MANUFACTURER") "PowerFilm Solar"))
      (libsource (lib "Swage") (part "SOLAR_PANEL"))
    )
    (comp (ref "SW1")
      (value "MK15-E-2")
      (footprint "MK15-E-2")
      (description "SWITCH REED MAG SMT 25-30 AT")
      (fields (field (name "MANUFACTURER") "Standex-Meder Electronics"))
      (libsource (lib "Swage") (part "MK15-E-2"))
    )
    (comp (ref "TP1")
      (value "Testpoint")
      (footprint "TestPoint")
      (libsource (lib "Swage") (part "Testpoint"))
    )
    (comp (ref "TP2")
      (value "Testpoint")
      (footprint "TestPoint")
      (libsource (lib "Swage") (part "Testpoint"))
    )
    (comp (ref "TP3")
      (value "Testpoint")
      (footprint "TestPoint")
      (libsource (lib "Swage") (part "Testpoint"))
    )
    (comp (ref "TP4")
      (value "Testpoint")
      (footprint "TestPoint")
      (libsource (lib "Swage") (part "Testpoint"))
    )
    (comp (ref "TP5")
      (value "Testpoint")
      (footprint "TestPoint")
      (libsource (lib "Swage") (part "Testpoint"))
    )
    (comp (ref "TP6")
      (value "Testpoint")
      (footprint "TestPoint")
      (libsource (lib "Swage") (part "Testpoint"))
    )
    (comp (ref "TP7")
      (value "Testpoint")
      (footprint "TestPoint")
      (libsource (lib "Swage") (part "Testpoint"))
    )
    (comp (ref "TP8")
      (value "Testpoint")
      (footprint "TestPoint")
      (libsource (lib "Swage") (part "Testpoint"))
    )
    (comp (ref "TP9")
      (value "Testpoint")
      (footprint "TestPoint")
      (libsource (lib "Swage") (part "Testpoint"))
    )
    (comp (ref "TP10")
      (value "Testpoint")
      (footprint "TestPoint")
      (libsource (lib "Swage") (part "Testpoint"))
    )
    (comp (ref "TP11")
      (value "Testpoint")
      (footprint "TestPoint")
      (libsource (lib "Swage") (part "Testpoint"))
    )
    (comp (ref "TP12")
      (value "Testpoint")
      (footprint "TestPoint")
      (libsource (lib "Swage") (part "Testpoint"))
    )
    (comp (ref "TP13")
      (value "Testpoint")
      (footprint "TestPoint")
      (libsource (lib "Swage") (part "Testpoint"))
    )
    (comp (ref "TP14")
      (value "Testpoint")
      (footprint "TestPoint")
      (libsource (lib "Swage") (part "Testpoint"))
    )
    (comp (ref "TP15")
      (value "Testpoint")
      (footprint "TestPoint")
      (libsource (lib "Swage") (part "Testpoint"))
    )
    (comp (ref "TP16")
      (value "Testpoint")
      (footprint "TestPoint")
      (libsource (lib "Swage") (part "Testpoint"))
    )
    (comp (ref "TP17")
      (value "Testpoint")
      (footprint "TestPoint")
      (libsource (lib "Swage") (part "Testpoint"))
    )
    (comp (ref "TP18")
      (value "Testpoint")
      (footprint "TestPoint")
      (libsource (lib "Swage") (part "Testpoint"))
    )
    (comp (ref "TP19")
      (value "Testpoint")
      (footprint "TestPoint")
      (libsource (lib "Swage") (part "Testpoint"))
    )
    (comp (ref "TP20")
      (value "Testpoint")
      (footprint "TestPoint")
      (libsource (lib "Swage") (part "Testpoint"))
    )
    (comp (ref "TP21")
      (value "Testpoint")
      (footprint "TestPoint")
      (libsource (lib "Swage") (part "Testpoint"))
    )
    (comp (ref "TP22")
      (value "Testpoint")
      (footprint "TestPoint")
      (libsource (lib "Swage") (part "Testpoint"))
    )
    (comp (ref "TP23")
      (value "Testpoint")
      (footprint "TestPoint")
      (libsource (lib "Swage") (part "Testpoint"))
    )
    (comp (ref "TP24")
      (value "Testpoint")
      (footprint "TestPoint")
      (libsource (lib "Swage") (part "Testpoint"))
    )
    (comp (ref "U1")
      (value "LTC3526LBEDC-2")
      (footprint "LTC3526")
      (description "IC REG BOOST SYNC ADJ 0.55A 6DFN")
      (fields
        (field (name "MANUFACTURER") "Linear Technology")
        (field (name "MANUFACTURER PART NUMBER") "LTC3526LBEDC-2#TRMPBF")
      )
      (libsource (lib "Swage") (part "LTC3526LBEDC-2"))
    )
    (comp (ref "U2")
      (value "BQ25504RGT")
      (footprint "BQ25504")
      (description "IC ENERGY HARV CTRLR BATT 16QFN")
      (fields
        (field (name "MANUFACTURER") "Texas Instruments")
        (field (name "MANUFACTURER PART NUMBER") "BQ25504RGTT")
      )
      (libsource (lib "Swage") (part "BQ25504RGTT"))
    )
    (comp (ref "U3")
      (value "FDG6342L")
      (footprint "TS5A3160")
      (description "IC LOAD SWITCH INTEGRATED SC70-6")
      (fields (field (name "MANUFACTURER") "Fairchild Semiconductor"))
      (libsource (lib "Swage") (part "FDG6342L"))
    )
    (comp (ref "U5")
      (value "FDG6342L")
      (footprint "TS5A3160")
      (description "IC LOAD SWITCH INTEGRATED SC70-6")
      (fields (field (name "MANUFACTURER") "Fairchild Semiconductor"))
      (libsource (lib "Swage") (part "FDG6342L"))
    )
    (comp (ref "U6")
      (value "DS2482S-100+")
      (footprint "SOIC127P580X153-8N")
      (description "IC BRIDGE I2C TO 1-WIRE 8-SOIC")
      (fields (field (name "MANUFACTURER") "Maxim Integrated"))
      (libsource (lib "Swage") (part "DS2482S-100+"))
    )
    (comp (ref "U8")
      (value "NLAS4157D")
      (footprint "TS5A3160")
      (description "IC SWITCH SPDT SC88")
      (fields
        (field (name "MANUFACTURER") "ON Semiconductor")
        (field (name "MANUFACTURER PART NUMBER") "NLAS4157DFT2G")
      )
      (libsource (lib "Swage") (part "NLAS4157DFT2G"))
    )
    (comp (ref "U9")
      (value "NLAS4157D")
      (footprint "TS5A3160")
      (description "IC SWITCH SPDT SC88")
      (fields
        (field (name "MANUFACTURER") "ON Semiconductor")
        (field (name "MANUFACTURER PART NUMBER") "NLAS4157DFT2G")
      )
      (libsource (lib "") (part "NLAS4157DFT2G_1"))
    )
    (comp (ref "U10")
      (value "PCA9306DP")
      (footprint "TSOP65P640X120-8N")
      (description "IC LEVEL TRANSLATOR - TSSOP8")
      (fields
        (field (name "MANUFACTURER") "ON Semiconductor")
        (field (name "MANUFACTURER PART NUMBER") "PCA9306DTR2G")
      )
      (libsource (lib "Swage") (part "PCA9306DP"))
    )
    (comp (ref "U11")
      (value "TPS3808G01DBV")
      (footprint "SOT95P270X145-6N")
      (description "Low Quiescent Current, Programmable-Delay  Supervisory Circuit")
      (fields
        (field (name "MANUFACTURER") "Texas Instruments")
        (field (name "MANUFACTURER PART NUMBER") "TPS3808G01DBVR")
      )
      (libsource (lib "Swage") (part "TPS3808G01DBV"))
    )
  )
  (nets
    (net (code "1") (name "/A2D_VBAT") (class "Default")
      (node (ref "P6") (pin "12") (pintype "passive"))
      (node (ref "R35") (pin "2") (pinfunction "2_2") (pintype "passive"))
      (node (ref "R37") (pin "2") (pinfunction "2_2") (pintype "passive"))
      (node (ref "RAD1") (pin "13") (pinfunction "GPIO11/ADC0/PF0_13") (pintype "passive"))
      (node (ref "TP11") (pin "1") (pinfunction "1_1") (pintype "passive"))
    )
    (net (code "2") (name "/A2D_VSOLAR") (class "Default")
      (node (ref "P6") (pin "7") (pintype "passive"))
      (node (ref "Q6") (pin "1") (pinfunction "D_1") (pintype "passive"))
      (node (ref "R36") (pin "2") (pinfunction "2_2") (pintype "passive"))
      (node (ref "R38") (pin "2") (pinfunction "2_2") (pintype "passive"))
      (node (ref "RAD1") (pin "18") (pinfunction "GPIO16/ADC5/TMS_18") (pintype "passive"))
      (node (ref "TP12") (pin "1") (pinfunction "1_1") (pintype "passive"))
    )
    (net (code "3") (name "/DQ_CHANNEL_0") (class "Default")
      (node (ref "D2") (pin "2") (pinfunction "2_2") (pintype "passive"))
      (node (ref "D8") (pin "2") (pinfunction "2_2") (pintype "passive"))
      (node (ref "P4") (pin "3") (pinfunction "DESIGNATOR=3_3") (pintype "passive"))
      (node (ref "P5") (pin "2") (pinfunction "2_2") (pintype "passive"))
      (node (ref "U8") (pin "4") (pinfunction "4_4") (pintype "passive"))
    )
    (net (code "4") (name "/DQ_CONNECT") (class "Default")
      (node (ref "P6") (pin "9") (pintype "passive"))
      (node (ref "R66") (pin "1") (pinfunction "1_1") (pintype "passive"))
      (node (ref "RAD1") (pin "16") (pinfunction "GPIO14/XCK0/AIN0_16") (pintype "passive"))
      (node (ref "TP17") (pin "1") (pinfunction "1_1") (pintype "passive"))
    )
    (net (code "5") (name "/DQ_DEFIB") (class "Default")
      (node (ref "P7") (pin "11") (pintype "passive"))
      (node (ref "R15") (pin "1") (pinfunction "1_1") (pintype "passive"))
      (node (ref "RAD1") (pin "11") (pinfunction "GPIO9/ICP1/PD4_11") (pintype "passive"))
      (node (ref "TP16") (pin "1") (pinfunction "1_1") (pintype "passive"))
    )
    (net (code "6") (name "/DQ_MASTER") (class "Default")
      (node (ref "Q1") (pin "D") (pinfunction "D_D") (pintype "passive"))
      (node (ref "R18") (pin "2") (pinfunction "2_2") (pintype "passive"))
      (node (ref "R54") (pin "2") (pinfunction "2_2") (pintype "passive"))
      (node (ref "U6") (pin "2") (pinfunction "IO_2") (pintype "passive"))
      (node (ref "U8") (pin "1") (pinfunction "NO_1") (pintype "passive"))
    )
    (net (code "7") (name "/GPIO7") (class "Default")
      (node (ref "P7") (pin "9") (pintype "passive"))
      (node (ref "R27") (pin "1") (pinfunction "1_1") (pintype "passive"))
      (node (ref "RAD1") (pin "9") (pinfunction "GPIO7/RXD1/PD2_9") (pintype "passive"))
    )
    (net (code "8") (name "/GPIO8") (class "Default")
      (node (ref "P7") (pin "10") (pintype "passive"))
      (node (ref "R28") (pin "1") (pinfunction "1_1") (pintype "passive"))
      (node (ref "RAD1") (pin "10") (pinfunction "GPIO8/TXD1/PD3_10") (pintype "passive"))
    )
    (net (code "9") (name "/GPIO15") (class "Default")
      (node (ref "P6") (pin "8") (pintype "passive"))
      (node (ref "R41") (pin "2") (pinfunction "2_2") (pintype "passive"))
      (node (ref "RAD1") (pin "17") (pinfunction "GPIO15/ADC4/TCK_17") (pintype "passive"))
    )
    (net (code "10") (name "/GPIO19") (class "Default")
      (node (ref "P6") (pin "3") (pintype "passive"))
      (node (ref "R40") (pin "2") (pinfunction "2_2") (pintype "passive"))
      (node (ref "RAD1") (pin "22") (pinfunction "GPIO19/OC3A/AIN1_22") (pintype "passive"))
    )
    (net (code "11") (name "/HW_VER1") (class "Default")
      (node (ref "P7") (pin "3") (pintype "passive"))
      (node (ref "R50") (pin "1") (pinfunction "1_1") (pintype "passive"))
      (node (ref "RAD1") (pin "3") (pinfunction "GPIO1/PCINT6/PB6_3") (pintype "passive"))
      (node (ref "TP21") (pin "1") (pinfunction "1_1") (pintype "passive"))
    )
    (net (code "12") (name "/HW_VER2") (class "Default")
      (node (ref "P7") (pin "5") (pintype "passive"))
      (node (ref "R51") (pin "1") (pinfunction "1_1") (pintype "passive"))
      (node (ref "RAD1") (pin "5") (pinfunction "GPIO3/RXD0/PE0_5") (pintype "passive"))
      (node (ref "TP22") (pin "1") (pinfunction "1_1") (pintype "passive"))
    )
    (net (code "13") (name "/HW_VER3") (class "Default")
      (node (ref "P7") (pin "6") (pintype "passive"))
      (node (ref "R52") (pin "1") (pinfunction "1_1") (pintype "passive"))
      (node (ref "RAD1") (pin "6") (pinfunction "GPIO4/TXD0/PE1_6") (pintype "passive"))
      (node (ref "TP23") (pin "1") (pinfunction "1_1") (pintype "passive"))
    )
    (net (code "14") (name "/HW_VER4") (class "Default")
      (node (ref "P7") (pin "8") (pintype "passive"))
      (node (ref "R53") (pin "1") (pinfunction "1_1") (pintype "passive"))
      (node (ref "RAD1") (pin "8") (pinfunction "GPIO6/INT5/PE5_8") (pintype "passive"))
      (node (ref "TP24") (pin "1") (pinfunction "1_1") (pintype "passive"))
    )
    (net (code "15") (name "/I2C_SCL") (class "Default")
      (node (ref "P6") (pin "5") (pintype "passive"))
      (node (ref "R68") (pin "1") (pinfunction "1_1") (pintype "passive"))
      (node (ref "RAD1") (pin "20") (pinfunction "GPIO18/ADC7/TDI_20") (pintype "passive"))
      (node (ref "TP15") (pin "1") (pinfunction "1_1") (pintype "passive"))
      (node (ref "U10") (pin "3") (pinfunction "SCL1_3") (pintype "passive"))
    )
    (net (code "16") (name "/I2C_SDA") (class "Default")
      (node (ref "P6") (pin "6") (pintype "passive"))
      (node (ref "R55") (pin "1") (pinfunction "1_1") (pintype "passive"))
      (node (ref "RAD1") (pin "19") (pinfunction "GPIO17/ADC6/TDO_19") (pintype "passive"))
      (node (ref "TP14") (pin "1") (pinfunction "1_1") (pintype "passive"))
      (node (ref "U10") (pin "4") (pinfunction "SDA1_4") (pintype "passive"))
    )
    (net (code "17") (name "/LED1") (class "Default")
      (node (ref "P7") (pin "7") (pintype "passive"))
      (node (ref "R25") (pin "1") (pinfunction "1_1") (pintype "passive"))
      (node (ref "RAD1") (pin "7") (pinfunction "GPIO5/INT4/PE4_7") (pintype "passive"))
      (node (ref "TP7") (pin "1") (pinfunction "1_1") (pintype "passive"))
    )
    (net (code "18") (name "/LED2") (class "Default")
      (node (ref "P7") (pin "2") (pintype "passive"))
      (node (ref "R26") (pin "1") (pinfunction "1_1") (pintype "passive"))
      (node (ref "RAD1") (pin "2") (pinfunction "GPIO0/PCINT7/PB7_2") (pintype "passive"))
      (node (ref "TP8") (pin "1") (pinfunction "1_1") (pintype "passive"))
    )
    (net (code "19") (name "/LED3") (class "Default")
      (node (ref "P7") (pin "4") (pintype "passive"))
      (node (ref "R30") (pin "1") (pinfunction "1_1") (pintype "passive"))
      (node (ref "RAD1") (pin "4") (pinfunction "GPIO2/PCINT5/PB5_4") (pintype "passive"))
      (node (ref "TP9") (pin "1") (pinfunction "1_1") (pintype "passive"))
    )
    (net (code "20") (name "/LED4") (class "Default")
      (node (ref "P6") (pin "10") (pintype "passive"))
      (node (ref "R33") (pin "1") (pinfunction "1_1") (pintype "passive"))
      (node (ref "RAD1") (pin "15") (pinfunction "GPIO13/ADC2/PF2_15") (pintype "passive"))
      (node (ref "TP10") (pin "1") (pinfunction "1_1") (pintype "passive"))
    )
    (net (code "21") (name "/N_5V_OFF") (class "Default")
      (node (ref "P7") (pin "12") (pintype "passive"))
      (node (ref "RAD1") (pin "12") (pinfunction "GPIO10/INT7/CLK0_12") (pintype "passive"))
      (node (ref "TP13") (pin "1") (pinfunction "1_1") (pintype "passive"))
      (node (ref "U1") (pin "4") (pinfunction "~{SHDN}_4") (pintype "passive"))
    )
    (net (code "22") (name "/POWER_IN") (class "Default")
      (node (ref "P4") (pin "7") (pinfunction "DESIGNATOR=7_7") (pintype "passive"))
      (node (ref "P5") (pin "1") (pinfunction "1_1") (pintype "passive"))
      (node (ref "R45") (pin "1") (pinfunction "1_1") (pintype "passive"))
    )
    (net (code "23") (name "/RXD_RF200") (class "Default")
      (node (ref "D13") (pin "3") (pinfunction "3_3") (pintype "passive"))
      (node (ref "P2") (pin "2") (pinfunction "2_2") (pintype "passive"))
      (node (ref "P4") (pin "11") (pinfunction "DESIGNATOR=11_11") (pintype "passive"))
      (node (ref "R27") (pin "2") (pinfunction "2_2") (pintype "passive"))
    )
    (net (code "24") (name "/SPARE1") (class "Default")
      (node (ref "P4") (pin "4") (pinfunction "DESIGNATOR=4_4") (pintype "passive"))
      (node (ref "R44") (pin "2") (pinfunction "2_2") (pintype "passive"))
    )
    (net (code "25") (name "/TXD_RF200") (class "Default")
      (node (ref "D11") (pin "3") (pinfunction "3_3") (pintype "passive"))
      (node (ref "P2") (pin "3") (pinfunction "3_3") (pintype "passive"))
      (node (ref "P4") (pin "9") (pinfunction "DESIGNATOR=9_9") (pintype "passive"))
      (node (ref "R28") (pin "2") (pinfunction "2_2") (pintype "passive"))
    )
    (net (code "26") (name "/VBAT_FUSED") (class "Default")
      (node (ref "F1") (pin "1") (pinfunction "1_1") (pintype "passive"))
      (node (ref "R13") (pin "2") (pinfunction "2_2") (pintype "passive"))
      (node (ref "R42") (pin "1") (pinfunction "1_1") (pintype "passive"))
      (node (ref "TP3") (pin "1") (pinfunction "1_1") (pintype "passive"))
      (node (ref "U3") (pin "4") (pinfunction "VIN_4") (pintype "passive"))
    )
    (net (code "27") (name "/VBAT_OK") (class "Default")
      (node (ref "D10") (pin "2") (pinfunction "2_2") (pintype "passive"))
      (node (ref "D9") (pin "1") (pintype "passive"))
      (node (ref "P1") (pin "1") (pinfunction "1_1") (pintype "passive"))
      (node (ref "R20") (pin "1") (pinfunction "1_1") (pintype "passive"))
      (node (ref "R47") (pin "2") (pinfunction "2_2") (pintype "passive"))
      (node (ref "R62") (pin "2") (pinfunction "2_2") (pintype "passive"))
      (node (ref "U3") (pin "5") (pinfunction "ON/~{OFF}_5") (pintype "passive"))
    )
    (net (code "28") (name "/VBAT_POS") (class "Default")
      (node (ref "BATT1") (pin "1") (pinfunction "1_1") (pintype "passive"))
      (node (ref "BATT1") (pin "2") (pinfunction "2_2") (pintype "passive"))
      (node (ref "BATT1") (pin "3") (pinfunction "3_3") (pintype "passive"))
      (node (ref "BATT1") (pin "4") (pinfunction "4_4") (pintype "passive"))
      (node (ref "F1") (pin "2") (pinfunction "2_2") (pintype "passive"))
      (node (ref "F3") (pin "1") (pinfunction "1_1") (pintype "passive"))
      (node (ref "J1") (pin "1") (pinfunction "1_1") (pintype "passive"))
    )
    (net (code "29") (name "/VBAT_SW_SENSE") (class "Default")
      (node (ref "P4") (pin "5") (pinfunction "DESIGNATOR=5_5") (pintype "passive"))
      (node (ref "R43") (pin "2") (pinfunction "2_2") (pintype "passive"))
    )
    (net (code "30") (name "/VIN_SOLAR") (class "Default")
      (node (ref "C2") (pin "2") (pinfunction "2_2") (pintype "passive"))
      (node (ref "D15") (pin "1") (pintype "passive"))
      (node (ref "D3") (pin "2") (pinfunction "K_2") (pintype "passive"))
      (node (ref "D4") (pin "2") (pinfunction "K_2") (pintype "passive"))
      (node (ref "D5") (pin "2") (pinfunction "2_2") (pintype "passive"))
      (node (ref "D6") (pin "1") (pintype "passive"))
      (node (ref "F2") (pin "1") (pinfunction "1_1") (pintype "passive"))
      (node (ref "L2") (pin "A") (pinfunction "A_A") (pintype "passive"))
      (node (ref "R2") (pin "2") (pinfunction "2_2") (pintype "passive"))
      (node (ref "R36") (pin "1") (pinfunction "1_1") (pintype "passive"))
      (node (ref "TP1") (pin "1") (pinfunction "1_1") (pintype "passive"))
      (node (ref "U2") (pin "2") (pinfunction "VIN_DC_2") (pintype "passive"))
    )
    (net (code "31") (name "/VSTOR") (class "Default")
      (node (ref "C3") (pin "2") (pinfunction "2_2") (pintype "passive"))
      (node (ref "TP2") (pin "1") (pinfunction "1_1") (pintype "passive"))
      (node (ref "U2") (pin "15") (pinfunction "VSTOR_15") (pintype "passive"))
    )
    (net (code "32") (name "/nBOOT_CNE") (class "Default")
      (node (ref "D14") (pin "3") (pinfunction "3_3") (pintype "passive"))
      (node (ref "P4") (pin "10") (pinfunction "DESIGNATOR=10_10") (pintype "passive"))
      (node (ref "R41") (pin "1") (pinfunction "1_1") (pintype "passive"))
    )
    (net (code "33") (name "/nRESET") (class "Default")
      (node (ref "P6") (pin "2") (pintype "passive"))
      (node (ref "R69") (pin "2") (pinfunction "2_2") (pintype "passive"))
      (node (ref "RAD1") (pin "23") (pinfunction "nRESET_23") (pintype "passive"))
      (node (ref "TP20") (pin "1") (pinfunction "1_1") (pintype "passive"))
      (node (ref "U11") (pin "1") (pinfunction "/RESET_1") (pintype "passive"))
      (node (ref "U9") (pin "4") (pinfunction "4_4") (pintype "passive"))
    )
    (net (code "34") (name "/nRESET_CNE") (class "Default")
      (node (ref "D12") (pin "3") (pinfunction "3_3") (pintype "passive"))
      (node (ref "P4") (pin "1") (pinfunction "DESIGNATOR=1_1") (pintype "passive"))
      (node (ref "R40") (pin "1") (pinfunction "1_1") (pintype "passive"))
    )
    (net (code "35") (name "5V") (class "Default")
      (node (ref "C1") (pin "2") (pinfunction "2_2") (pintype "passive"))
      (node (ref "C10") (pin "2") (pinfunction "2_2") (pintype "passive"))
      (node (ref "C5") (pin "2") (pinfunction "2_2") (pintype "passive"))
      (node (ref "D16") (pin "1") (pinfunction "A_1") (pintype "passive"))
      (node (ref "P4") (pin "8") (pinfunction "DESIGNATOR=8_8") (pintype "passive"))
      (node (ref "R1") (pin "2") (pinfunction "2_2") (pintype "passive"))
      (node (ref "R16") (pin "2") (pinfunction "2_2") (pintype "passive"))
      (node (ref "R17") (pin "1") (pinfunction "1_1") (pintype "passive"))
      (node (ref "R21") (pin "1") (pinfunction "1_1") (pintype "passive"))
      (node (ref "R22") (pin "1") (pinfunction "1_1") (pintype "passive"))
      (node (ref "R29") (pin "1") (pinfunction "1_1") (pintype "passive"))
      (node (ref "R32") (pin "1") (pinfunction "1_1") (pintype "passive"))
      (node (ref "R46") (pin "1") (pinfunction "1_1") (pintype "passive"))
      (node (ref "R54") (pin "1") (pinfunction "1_1") (pintype "passive"))
      (node (ref "R56") (pin "2") (pinfunction "2_2") (pintype "passive"))
      (node (ref "R57") (pin "2") (pinfunction "2_2") (pintype "passive"))
      (node (ref "R58") (pin "1") (pinfunction "1_1") (pintype "passive"))
      (node (ref "TP4") (pin "1") (pinfunction "1_1") (pintype "passive"))
      (node (ref "U1") (pin "6") (pinfunction "VOUT_6") (pintype "passive"))
      (node (ref "U5") (pin "4") (pinfunction "VIN_4") (pintype "passive"))
      (node (ref "U6") (pin "1") (pinfunction "VCC_1") (pintype "passive"))
    )
    (net (code "36") (name "CONSTANT_POWER") (class "Default")
      (node (ref "C11") (pin "1") (pinfunction "1_1") (pintype "passive"))
      (node (ref "D16") (pin "3") (pinfunction "K_3") (pintype "passive"))
      (node (ref "R46") (pin "2") (pinfunction "2_2") (pintype "passive"))
      (node (ref "TP5") (pin "1") (pinfunction "1_1") (pintype "passive"))
      (node (ref "U8") (pin "5") (pinfunction "5_5") (pintype "passive"))
    )
    (net (code "37") (name "GND") (class "Default")
      (node (ref "BATT1") (pin "5") (pinfunction "5_5") (pintype "passive"))
      (node (ref "BATT1") (pin "6") (pinfunction "6_6") (pintype "passive"))
      (node (ref "BATT1") (pin "7") (pinfunction "7_7") (pintype "passive"))
      (node (ref "BATT1") (pin "8") (pinfunction "8_8") (pintype "passive"))
      (node (ref "C10") (pin "1") (pinfunction "1_1") (pintype "passive"))
      (node (ref "C11") (pin "2") (pinfunction "2_2") (pintype "passive"))
      (node (ref "C2") (pin "1") (pinfunction "1_1") (pintype "passive"))
      (node (ref "C20") (pin "1") (pinfunction "1_1") (pintype "passive"))
      (node (ref "C3") (pin "1") (pinfunction "1_1") (pintype "passive"))
      (node (ref "C4") (pin "1") (pinfunction "1_1") (pintype "passive"))
      (node (ref "C5") (pin "1") (pinfunction "1_1") (pintype "passive"))
      (node (ref "C50") (pin "1") (pinfunction "1_1") (pintype "passive"))
      (node (ref "C51") (pin "1") (pinfunction "1_1") (pintype "passive"))
      (node (ref "C53") (pin "1") (pinfunction "1_1") (pintype "passive"))
      (node (ref "C54") (pin "1") (pinfunction "1_1") (pintype "passive"))
      (node (ref "C6") (pin "1") (pinfunction "1_1") (pintype "passive"))
      (node (ref "C8") (pin "1") (pinfunction "1_1") (pintype "passive"))
      (node (ref "C9") (pin "1") (pinfunction "1_1") (pintype "passive"))
      (node (ref "D10") (pin "1") (pintype "passive"))
      (node (ref "D11") (pin "1") (pinfunction "A_1") (pintype "passive"))
      (node (ref "D12") (pin "1") (pinfunction "A_1") (pintype "passive"))
      (node (ref "D13") (pin "1") (pinfunction "A_1") (pintype "passive"))
      (node (ref "D14") (pin "1") (pinfunction "A_1") (pintype "passive"))
      (node (ref "D15") (pin "2") (pintype "passive"))
      (node (ref "D2") (pin "1") (pintype "passive"))
      (node (ref "D5") (pin "1") (pintype "passive"))
      (node (ref "D6") (pin "2") (pinfunction "2_2") (pintype "passive"))
      (node (ref "D8") (pin "1") (pintype "passive"))
      (node (ref "D9") (pin "2") (pinfunction "2_2") (pintype "passive"))
      (node (ref "J1") (pin "2") (pinfunction "2_2") (pintype "passive"))
      (node (ref "MH3") (pin "1") (pinfunction "1_1") (pintype "passive"))
      (node (ref "P1") (pin "2") (pinfunction "2_2") (pintype "passive"))
      (node (ref "P2") (pin "4") (pinfunction "4_4") (pintype "passive"))
      (node (ref "P3") (pin "1") (pinfunction "1_1") (pintype "passive"))
      (node (ref "P4") (pin "12") (pinfunction "DESIGNATOR=12_12") (pintype "passive"))
      (node (ref "P4") (pin "2") (pinfunction "DESIGNATOR=2_2") (pintype "passive"))
      (node (ref "P5") (pin "3") (pinfunction "3_3") (pintype "passive"))
      (node (ref "P6") (pin "1") (pintype "passive"))
      (node (ref "P7") (pin "1") (pintype "passive"))
      (node (ref "Q2") (pin "2") (pinfunction "S_2") (pintype "passive"))
      (node (ref "Q3") (pin "2") (pinfunction "S_2") (pintype "passive"))
      (node (ref "Q4") (pin "2") (pinfunction "S_2") (pintype "passive"))
      (node (ref "Q5") (pin "2") (pinfunction "S_2") (pintype "passive"))
      (node (ref "Q6") (pin "2") (pinfunction "S_2") (pintype "passive"))
      (node (ref "R10") (pin "2") (pinfunction "2_2") (pintype "passive"))
      (node (ref "R11") (pin "2") (pinfunction "2_2") (pintype "passive"))
      (node (ref "R12") (pin "2") (pinfunction "2_2") (pintype "passive"))
      (node (ref "R19") (pin "2") (pinfunction "2_2") (pintype "passive"))
      (node (ref "R23") (pin "2") (pinfunction "2_2") (pintype "passive"))
      (node (ref "R24") (pin "2") (pinfunction "2_2") (pintype "passive"))
      (node (ref "R3") (pin "2") (pinfunction "2_2") (pintype "passive"))
      (node (ref "R31") (pin "2") (pinfunction "2_2") (pintype "passive"))
      (node (ref "R34") (pin "2") (pinfunction "2_2") (pintype "passive"))
      (node (ref "R37") (pin "1") (pinfunction "1_1") (pintype "passive"))
      (node (ref "R38") (pin "1") (pinfunction "1_1") (pintype "passive"))
      (node (ref "R39") (pin "2") (pinfunction "2_2") (pintype "passive"))
      (node (ref "R44") (pin "1") (pinfunction "1_1") (pintype "passive"))
      (node (ref "R50") (pin "2") (pinfunction "2_2") (pintype "passive"))
      (node (ref "R51") (pin "2") (pinfunction "2_2") (pintype "passive"))
      (node (ref "R52") (pin "2") (pinfunction "2_2") (pintype "passive"))
      (node (ref "R53") (pin "2") (pinfunction "2_2") (pintype "passive"))
      (node (ref "R60") (pin "2") (pinfunction "2_2") (pintype "passive"))
      (node (ref "R65") (pin "1") (pinfunction "1_1") (pintype "passive"))
      (node (ref "R67") (pin "2") (pinfunction "2_2") (pintype "passive"))
      (node (ref "R7") (pin "2") (pinfunction "2_2") (pintype "passive"))
      (node (ref "RAD1") (pin "1") (pinfunction "GND_1") (pintype "passive"))
      (node (ref "RAD1") (pin "24") (pinfunction "GND_24") (pintype "passive"))
      (node (ref "SP1") (pin "1") (pinfunction "GND_1") (pintype "passive"))
      (node (ref "SW1") (pin "1") (pinfunction "1_1") (pintype "passive"))
      (node (ref "TP18") (pin "1") (pinfunction "1_1") (pintype "passive"))
      (node (ref "U1") (pin "2") (pinfunction "GND_2") (pintype "passive"))
      (node (ref "U1") (pin "7") (pinfunction "DIE_7") (pintype "passive"))
      (node (ref "U10") (pin "1") (pinfunction "GND_1") (pintype "passive"))
      (node (ref "U11") (pin "2") (pinfunction "GND_2") (pintype "passive"))
      (node (ref "U2") (pin "1") (pinfunction "GND_1") (pintype "passive"))
      (node (ref "U2") (pin "12") (pinfunction "AGND_12") (pintype "passive"))
      (node (ref "U2") (pin "13") (pinfunction "GND_13") (pintype "passive"))
      (node (ref "U2") (pin "17") (pinfunction "DIE_17") (pintype "passive"))
      (node (ref "U2") (pin "5") (pinfunction "OT_PROG_5") (pintype "passive"))
      (node (ref "U5") (pin "1") (pinfunction "R2_1") (pintype "passive"))
      (node (ref "U6") (pin "3") (pinfunction "GND_3") (pintype "passive"))
      (node (ref "U6") (pin "7") (pinfunction "AD1_7") (pintype "passive"))
      (node (ref "U6") (pin "8") (pinfunction "AD0_8") (pintype "passive"))
      (node (ref "U8") (pin "2") (pinfunction "GND_2") (pintype "passive"))
      (node (ref "U9") (pin "2") (pinfunction "GND_2") (pintype "passive"))
    )
    (net (code "38") (name "Net-(D1-A)") (class "Default")
      (node (ref "D1") (pin "1") (pinfunction "A_1") (pintype "passive"))
      (node (ref "P2") (pin "1") (pinfunction "1_1") (pintype "passive"))
      (node (ref "R45") (pin "2") (pinfunction "2_2") (pintype "passive"))
    )
    (net (code "39") (name "Net-(D1-K)") (class "Default")
      (node (ref "D1") (pin "2") (pinfunction "K_2") (pintype "passive"))
      (node (ref "F2") (pin "2") (pinfunction "2_2") (pintype "passive"))
    )
    (net (code "40") (name "Net-(D3-A)") (class "Default")
      (node (ref "D3") (pin "1") (pinfunction "A_1") (pintype "passive"))
      (node (ref "SP1") (pin "3") (pinfunction "4.8V_3") (pintype "passive"))
    )
    (net (code "41") (name "Net-(D4-A)") (class "Default")
      (node (ref "D4") (pin "1") (pinfunction "A_1") (pintype "passive"))
      (node (ref "SP1") (pin "2") (pinfunction "3.6V_2") (pintype "passive"))
    )
    (net (code "42") (name "Net-(LED1-PadA)") (class "Default")
      (node (ref "LED1") (pin "A") (pintype "passive"))
      (node (ref "R21") (pin "2") (pinfunction "2_2") (pintype "passive"))
    )
    (net (code "43") (name "Net-(LED2-PadA)") (class "Default")
      (node (ref "LED2") (pin "A") (pintype "passive"))
      (node (ref "R22") (pin "2") (pinfunction "2_2") (pintype "passive"))
    )
    (net (code "44") (name "Net-(LED3-PadA)") (class "Default")
      (node (ref "LED3") (pin "A") (pintype "passive"))
      (node (ref "R29") (pin "2") (pinfunction "2_2") (pintype "passive"))
    )
    (net (code "45") (name "Net-(LED4-PadA)") (class "Default")
      (node (ref "LED4") (pin "A") (pintype "passive"))
      (node (ref "R32") (pin "2") (pinfunction "2_2") (pintype "passive"))
    )
    (net (code "46") (name "Net-(Q1-PadS)") (class "Default")
      (node (ref "Q1") (pin "S") (pinfunction "S_S") (pintype "passive"))
      (node (ref "R17") (pin "2") (pinfunction "2_2") (pintype "passive"))
    )
    (net (code "47") (name "Net-(Q2-D)") (class "Default")
      (node (ref "LED1") (pin "K") (pintype "passive"))
      (node (ref "Q2") (pin "3") (pinfunction "D_3") (pintype "passive"))
    )
    (net (code "48") (name "Net-(Q2-G)") (class "Default")
      (node (ref "Q2") (pin "1") (pinfunction "G_1") (pintype "passive"))
      (node (ref "R23") (pin "1") (pinfunction "1_1") (pintype "passive"))
      (node (ref "R25") (pin "2") (pinfunction "2_2") (pintype "passive"))
    )
    (net (code "49") (name "Net-(Q3-D)") (class "Default")
      (node (ref "LED2") (pin "K") (pintype "passive"))
      (node (ref "Q3") (pin "3") (pinfunction "D_3") (pintype "passive"))
    )
    (net (code "50") (name "Net-(Q3-G)") (class "Default")
      (node (ref "Q3") (pin "1") (pinfunction "G_1") (pintype "passive"))
      (node (ref "R24") (pin "1") (pinfunction "1_1") (pintype "passive"))
      (node (ref "R26") (pin "2") (pinfunction "2_2") (pintype "passive"))
    )
    (net (code "51") (name "Net-(Q4-D)") (class "Default")
      (node (ref "LED3") (pin "K") (pintype "passive"))
      (node (ref "Q4") (pin "3") (pinfunction "D_3") (pintype "passive"))
    )
    (net (code "52") (name "Net-(Q4-G)") (class "Default")
      (node (ref "Q4") (pin "1") (pinfunction "G_1") (pintype "passive"))
      (node (ref "R30") (pin "2") (pinfunction "2_2") (pintype "passive"))
      (node (ref "R31") (pin "1") (pinfunction "1_1") (pintype "passive"))
    )
    (net (code "53") (name "Net-(Q5-D)") (class "Default")
      (node (ref "LED4") (pin "K") (pintype "passive"))
      (node (ref "Q5") (pin "3") (pinfunction "D_3") (pintype "passive"))
    )
    (net (code "54") (name "Net-(Q5-G)") (class "Default")
      (node (ref "Q5") (pin "1") (pinfunction "G_1") (pintype "passive"))
      (node (ref "R33") (pin "2") (pinfunction "2_2") (pintype "passive"))
      (node (ref "R34") (pin "1") (pinfunction "1_1") (pintype "passive"))
    )
    (net (code "55") (name "Net-(Q6-G)") (class "Default")
      (node (ref "Q6") (pin "3") (pinfunction "G_3") (pintype "passive"))
      (node (ref "R47") (pin "1") (pinfunction "1_1") (pintype "passive"))
    )
    (net (code "56") (name "Net-(R10-Pad1)") (class "Default")
      (node (ref "R10") (pin "1") (pinfunction "1_1") (pintype "passive"))
      (node (ref "R4") (pin "1") (pinfunction "1_1") (pintype "passive"))
    )
    (net (code "57") (name "Net-(R18-Pad1)") (class "Default")
      (node (ref "R18") (pin "1") (pinfunction "1_1") (pintype "passive"))
      (node (ref "U5") (pin "2") (pinfunction "VOUT_2") (pintype "passive"))
      (node (ref "U5") (pin "3") (pinfunction "VOUT_3") (pintype "passive"))
    )
    (net (code "58") (name "Net-(R62-Pad1)") (class "Default")
      (node (ref "R62") (pin "1") (pinfunction "1_1") (pintype "passive"))
      (node (ref "U9") (pin "6") (pinfunction "6_6") (pintype "passive"))
    )
    (net (code "59") (name "Net-(R66-Pad2)") (class "Default")
      (node (ref "R66") (pin "2") (pinfunction "2_2") (pintype "passive"))
      (node (ref "R67") (pin "1") (pinfunction "1_1") (pintype "passive"))
      (node (ref "U8") (pin "6") (pinfunction "6_6") (pintype "passive"))
    )
    (net (code "60") (name "Net-(U1-FB)") (class "Default")
      (node (ref "C1") (pin "1") (pinfunction "1_1") (pintype "passive"))
      (node (ref "R1") (pin "1") (pinfunction "1_1") (pintype "passive"))
      (node (ref "R3") (pin "1") (pinfunction "1_1") (pintype "passive"))
      (node (ref "U1") (pin "5") (pinfunction "FB_5") (pintype "passive"))
    )
    (net (code "61") (name "Net-(U1-SW)") (class "Default")
      (node (ref "L1") (pin "B") (pinfunction "B_B") (pintype "passive"))
      (node (ref "U1") (pin "1") (pinfunction "SW_1") (pintype "passive"))
    )
    (net (code "62") (name "Net-(U2-LBST)") (class "Default")
      (node (ref "L2") (pin "B") (pinfunction "B_B") (pintype "passive"))
      (node (ref "U2") (pin "16") (pinfunction "LBST_16") (pintype "passive"))
    )
    (net (code "63") (name "Net-(U2-OK_HYST)") (class "Default")
      (node (ref "R5") (pin "1") (pinfunction "1_1") (pintype "passive"))
      (node (ref "R6") (pin "2") (pinfunction "2_2") (pintype "passive"))
      (node (ref "U2") (pin "9") (pinfunction "OK_HYST_9") (pintype "passive"))
    )
    (net (code "64") (name "Net-(U2-OK_PROG)") (class "Default")
      (node (ref "R6") (pin "1") (pinfunction "1_1") (pintype "passive"))
      (node (ref "R7") (pin "1") (pinfunction "1_1") (pintype "passive"))
      (node (ref "U2") (pin "10") (pinfunction "OK_PROG_10") (pintype "passive"))
    )
    (net (code "65") (name "Net-(U2-VBAT)") (class "Default")
      (node (ref "F3") (pin "2") (pinfunction "2_2") (pintype "passive"))
      (node (ref "U2") (pin "14") (pinfunction "VBAT_14") (pintype "passive"))
    )
    (net (code "66") (name "Net-(U2-VBAT_OK)") (class "Default")
      (node (ref "R20") (pin "2") (pinfunction "2_2") (pintype "passive"))
      (node (ref "U2") (pin "11") (pinfunction "VBAT_OK_11") (pintype "passive"))
    )
    (net (code "67") (name "Net-(U2-VBAT_OV)") (class "Default")
      (node (ref "R11") (pin "1") (pinfunction "1_1") (pintype "passive"))
      (node (ref "R8") (pin "2") (pinfunction "2_2") (pintype "passive"))
      (node (ref "U2") (pin "6") (pinfunction "VBAT_OV_6") (pintype "passive"))
    )
    (net (code "68") (name "Net-(U2-VBAT_UV)") (class "Default")
      (node (ref "R12") (pin "1") (pinfunction "1_1") (pintype "passive"))
      (node (ref "R9") (pin "1") (pinfunction "1_1") (pintype "passive"))
      (node (ref "U2") (pin "8") (pinfunction "VBAT_UV_8") (pintype "passive"))
    )
    (net (code "69") (name "Net-(U2-VOC_SAMP)") (class "Default")
      (node (ref "R2") (pin "1") (pinfunction "1_1") (pintype "passive"))
      (node (ref "R4") (pin "2") (pinfunction "2_2") (pintype "passive"))
      (node (ref "U2") (pin "3") (pinfunction "VOC_SAMP_3") (pintype "passive"))
    )
    (net (code "70") (name "Net-(U2-VRDIV)") (class "Default")
      (node (ref "R5") (pin "2") (pinfunction "2_2") (pintype "passive"))
      (node (ref "R8") (pin "1") (pinfunction "1_1") (pintype "passive"))
      (node (ref "R9") (pin "2") (pinfunction "2_2") (pintype "passive"))
      (node (ref "U2") (pin "7") (pinfunction "VRDIV_7") (pintype "passive"))
    )
    (net (code "71") (name "Net-(U2-VREF_SAMP)") (class "Default")
      (node (ref "C6") (pin "2") (pinfunction "2_2") (pintype "passive"))
      (node (ref "U2") (pin "4") (pinfunction "VREF_SAMP_4") (pintype "passive"))
    )
    (net (code "72") (name "Net-(U3-R1C1)") (class "Default")
      (node (ref "C7") (pin "2") (pinfunction "2_2") (pintype "passive"))
      (node (ref "R13") (pin "1") (pinfunction "1_1") (pintype "passive"))
      (node (ref "U3") (pin "6") (pinfunction "R1C1_6") (pintype "passive"))
    )
    (net (code "73") (name "Net-(U3-R2)") (class "Default")
      (node (ref "R19") (pin "1") (pinfunction "1_1") (pintype "passive"))
      (node (ref "U3") (pin "1") (pinfunction "R2_1") (pintype "passive"))
    )
    (net (code "74") (name "Net-(U5-ON{slash}~{OFF})") (class "Default")
      (node (ref "R15") (pin "2") (pinfunction "2_2") (pintype "passive"))
      (node (ref "U5") (pin "5") (pinfunction "ON/~{OFF}_5") (pintype "passive"))
    )
    (net (code "75") (name "Net-(U5-R1C1)") (class "Default")
      (node (ref "R16") (pin "1") (pinfunction "1_1") (pintype "passive"))
      (node (ref "U5") (pin "6") (pinfunction "R1C1_6") (pintype "passive"))
    )
    (net (code "76") (name "Net-(U6-PCTLZ)") (class "Default")
      (node (ref "Q1") (pin "G") (pinfunction "G_G") (pintype "passive"))
      (node (ref "TP6") (pin "1") (pinfunction "1_1") (pintype "passive"))
      (node (ref "U6") (pin "6") (pinfunction "PCTLZ_6") (pintype "passive"))
    )
    (net (code "77") (name "Net-(U8-NC)") (class "Default")
      (node (ref "R39") (pin "1") (pinfunction "1_1") (pintype "passive"))
      (node (ref "U8") (pin "3") (pinfunction "NC_3") (pintype "passive"))
    )
    (net (code "78") (name "Net-(U9-NC)") (class "Default")
      (node (ref "R60") (pin "1") (pinfunction "1_1") (pintype "passive"))
      (node (ref "U9") (pin "3") (pinfunction "NC_3") (pintype "passive"))
    )
    (net (code "79") (name "Net-(U10-EN)") (class "Default")
      (node (ref "C20") (pin "2") (pinfunction "2_2") (pintype "passive"))
      (node (ref "R58") (pin "2") (pinfunction "2_2") (pintype "passive"))
      (node (ref "U10") (pin "7") (pinfunction "VREF2_7") (pintype "passive"))
      (node (ref "U10") (pin "8") (pinfunction "EN_8") (pintype "passive"))
    )
    (net (code "80") (name "Net-(U10-SCL2)") (class "Default")
      (node (ref "R56") (pin "1") (pinfunction "1_1") (pintype "passive"))
      (node (ref "U10") (pin "6") (pinfunction "SCL2_6") (pintype "passive"))
      (node (ref "U6") (pin "4") (pinfunction "SCL_4") (pintype "passive"))
    )
    (net (code "81") (name "Net-(U10-SDA2)") (class "Default")
      (node (ref "R57") (pin "1") (pinfunction "1_1") (pintype "passive"))
      (node (ref "U10") (pin "5") (pinfunction "SDA2_5") (pintype "passive"))
      (node (ref "U6") (pin "5") (pinfunction "SDA_5") (pintype "passive"))
    )
    (net (code "82") (name "Net-(U11-CT)") (class "Default")
      (node (ref "C50") (pin "2") (pinfunction "2_2") (pintype "passive"))
      (node (ref "U11") (pin "4") (pinfunction "CT_4") (pintype "passive"))
    )
    (net (code "83") (name "Net-(U11-SENSE)") (class "Default")
      (node (ref "C52") (pin "1") (pinfunction "1_1") (pintype "passive"))
      (node (ref "C54") (pin "2") (pinfunction "2_2") (pintype "passive"))
      (node (ref "R64") (pin "2") (pinfunction "2_2") (pintype "passive"))
      (node (ref "R65") (pin "2") (pinfunction "2_2") (pintype "passive"))
      (node (ref "U11") (pin "5") (pinfunction "SENSE_5") (pintype "passive"))
    )
    (net (code "84") (name "Net-(U11-{slash}MR)") (class "Default")
      (node (ref "C9") (pin "2") (pinfunction "2_2") (pintype "passive"))
      (node (ref "P3") (pin "2") (pinfunction "2_2") (pintype "passive"))
      (node (ref "R63") (pin "2") (pinfunction "2_2") (pintype "passive"))
      (node (ref "SW1") (pin "2") (pinfunction "2_2") (pintype "passive"))
      (node (ref "U11") (pin "3") (pinfunction "/MR_3") (pintype "passive"))
    )
    (net (code "85") (name "VBAT_SENSE") (class "Default")
      (node (ref "P4") (pin "6") (pinfunction "DESIGNATOR=6_6") (pintype "passive"))
      (node (ref "R42") (pin "2") (pinfunction "2_2") (pintype "passive"))
      (node (ref "U9") (pin "5") (pinfunction "5_5") (pintype "passive"))
    )
    (net (code "86") (name "VBAT_SWITCHED") (class "Default")
      (node (ref "C4") (pin "2") (pinfunction "2_2") (pintype "passive"))
      (node (ref "C51") (pin "2") (pinfunction "2_2") (pintype "passive"))
      (node (ref "C52") (pin "2") (pinfunction "2_2") (pintype "passive"))
      (node (ref "C53") (pin "2") (pinfunction "2_2") (pintype "passive"))
      (node (ref "C7") (pin "1") (pinfunction "1_1") (pintype "passive"))
      (node (ref "C8") (pin "2") (pinfunction "2_2") (pintype "passive"))
      (node (ref "D11") (pin "2") (pinfunction "K_2") (pintype "passive"))
      (node (ref "D12") (pin "2") (pinfunction "K_2") (pintype "passive"))
      (node (ref "D13") (pin "2") (pinfunction "K_2") (pintype "passive"))
      (node (ref "D14") (pin "2") (pinfunction "K_2") (pintype "passive"))
      (node (ref "D16") (pin "2") (pinfunction "A_2") (pintype "passive"))
      (node (ref "L1") (pin "A") (pinfunction "A_A") (pintype "passive"))
      (node (ref "P6") (pin "4") (pintype "passive"))
      (node (ref "R35") (pin "1") (pinfunction "1_1") (pintype "passive"))
      (node (ref "R43") (pin "1") (pinfunction "1_1") (pintype "passive"))
      (node (ref "R55") (pin "2") (pinfunction "2_2") (pintype "passive"))
      (node (ref "R63") (pin "1") (pinfunction "1_1") (pintype "passive"))
      (node (ref "R64") (pin "1") (pinfunction "1_1") (pintype "passive"))
      (node (ref "R68") (pin "2") (pinfunction "2_2") (pintype "passive"))
      (node (ref "R69") (pin "1") (pinfunction "1_1") (pintype "passive"))
      (node (ref "RAD1") (pin "21") (pinfunction "VCC_21") (pintype "passive"))
      (node (ref "TP19") (pin "1") (pinfunction "1_1") (pintype "passive"))
      (node (ref "U1") (pin "3") (pinfunction "VIN_3") (pintype "passive"))
      (node (ref "U10") (pin "2") (pinfunction "VREF1_2") (pintype "passive"))
      (node (ref "U11") (pin "6") (pinfunction "VDD_6") (pintype "passive"))
      (node (ref "U3") (pin "2") (pinfunction "VOUT_2") (pintype "passive"))
      (node (ref "U3") (pin "3") (pinfunction "VOUT_3") (pintype "passive"))
    )
    (net (code "87") (name "unconnected-(D3-Pad3)") (class "Default")
      (node (ref "D3") (pin "3") (pinfunction "3_3") (pintype "passive+no_connect"))
    )
    (net (code "88") (name "unconnected-(MH1-Pad1)") (class "Default")
      (node (ref "MH1") (pin "1") (pinfunction "1_1") (pintype "passive"))
    )
    (net (code "89") (name "unconnected-(MH2-Pad1)") (class "Default")
      (node (ref "MH2") (pin "1") (pinfunction "1_1") (pintype "passive"))
    )
    (net (code "90") (name "unconnected-(P6-Pad11)") (class "Default")
      (node (ref "P6") (pin "11") (pintype "passive"))
    )
    (net (code "91") (name "unconnected-(RAD1-GPIO12{slash}ADC1{slash}PF1-Pad14)") (class "Default")
      (node (ref "RAD1") (pin "14") (pinfunction "GPIO12/ADC1/PF1_14") (pintype "passive"))
    )
    (net (code "92") (name "unconnected-(U9-NO-Pad1)") (class "Default")
      (node (ref "U9") (pin "1") (pinfunction "NO_1") (pintype "passive"))
    )
  )
)
